# RUMBA_plus.net
KiCad netlist of a schematic drawn in Altium Designer
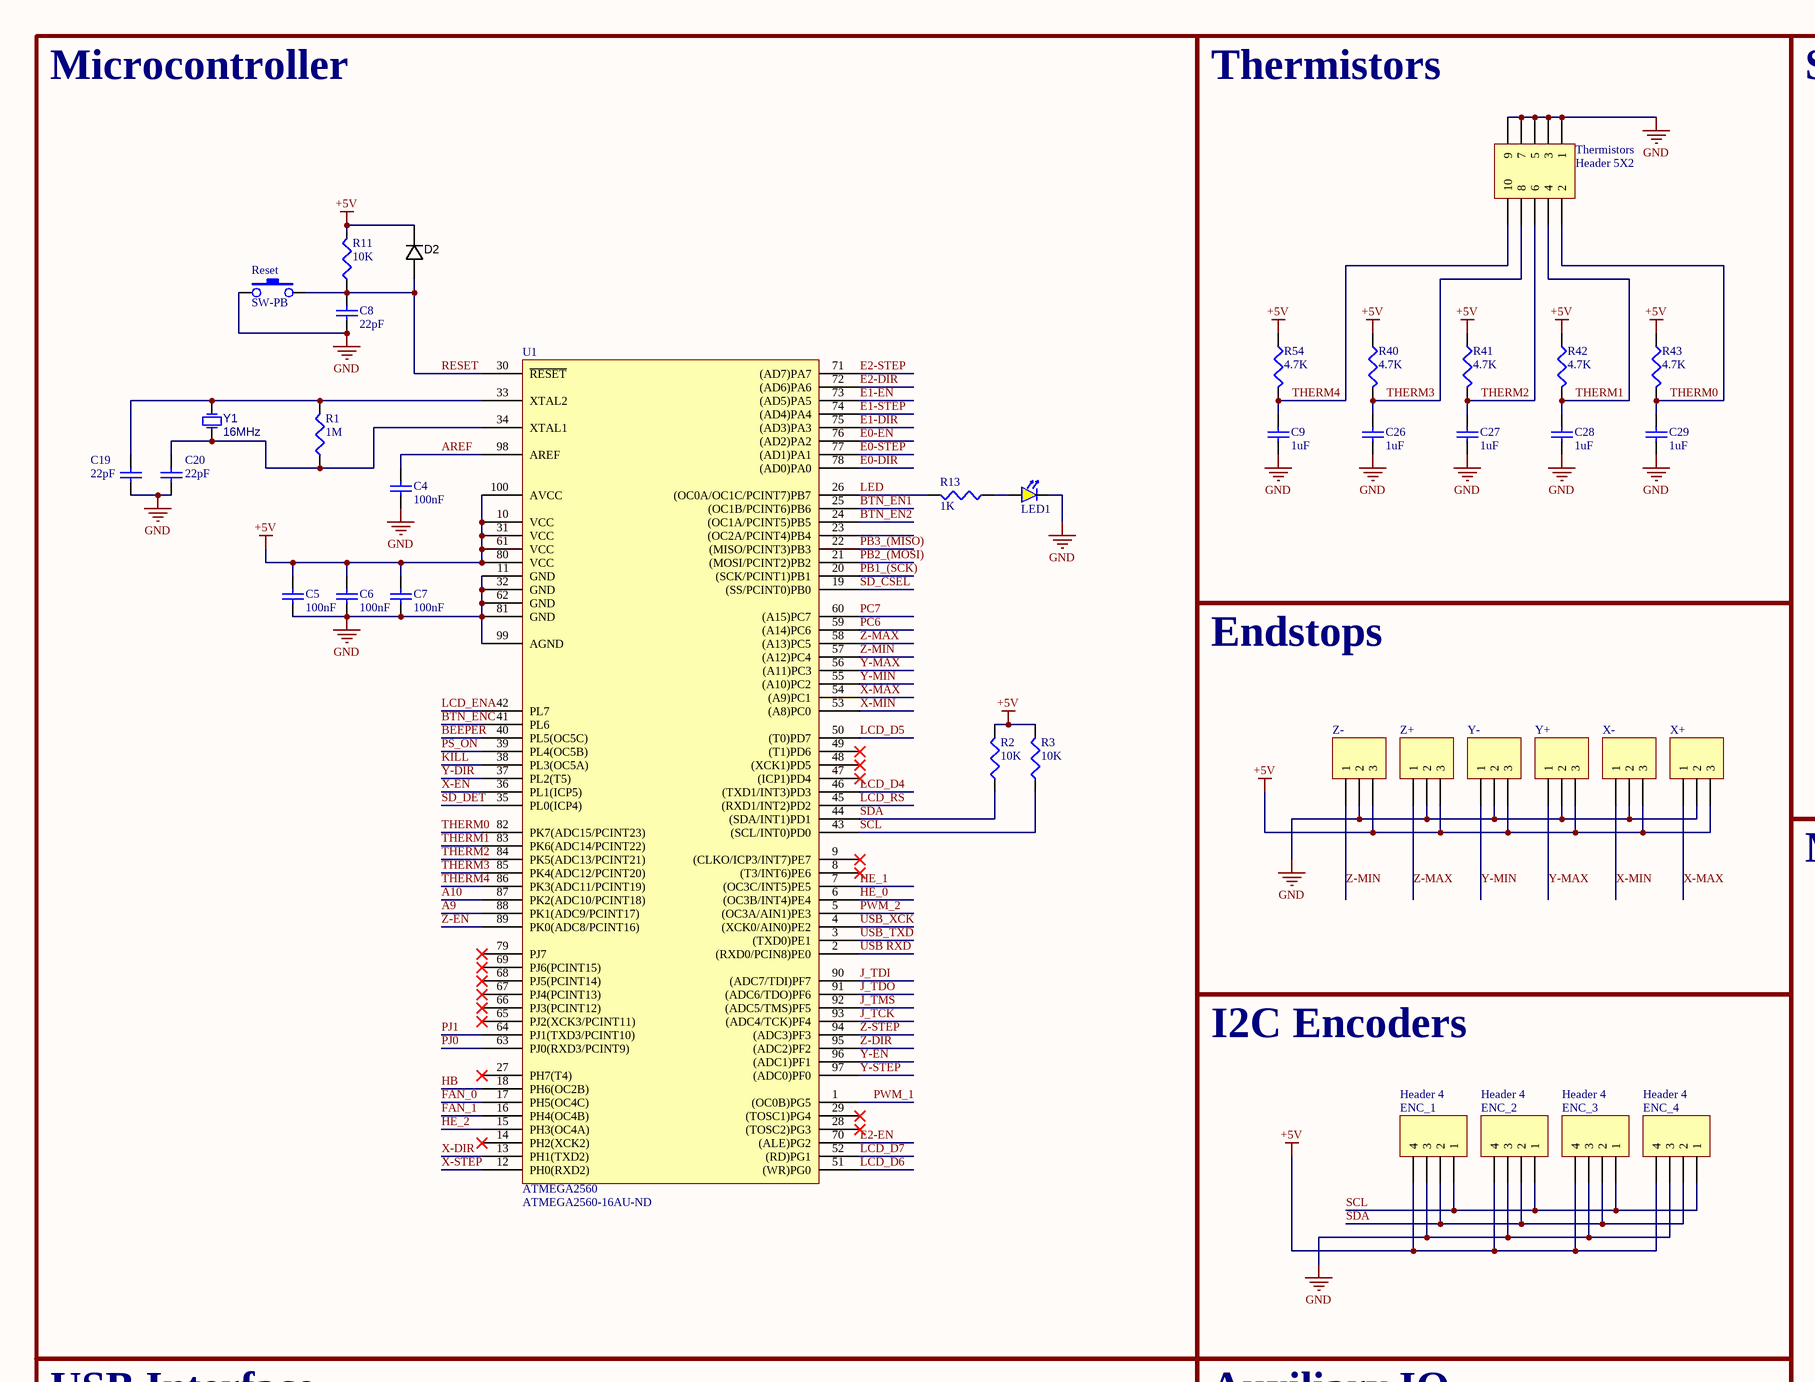
[diagram p0: RUMBA_plus.SchDoc, top left]
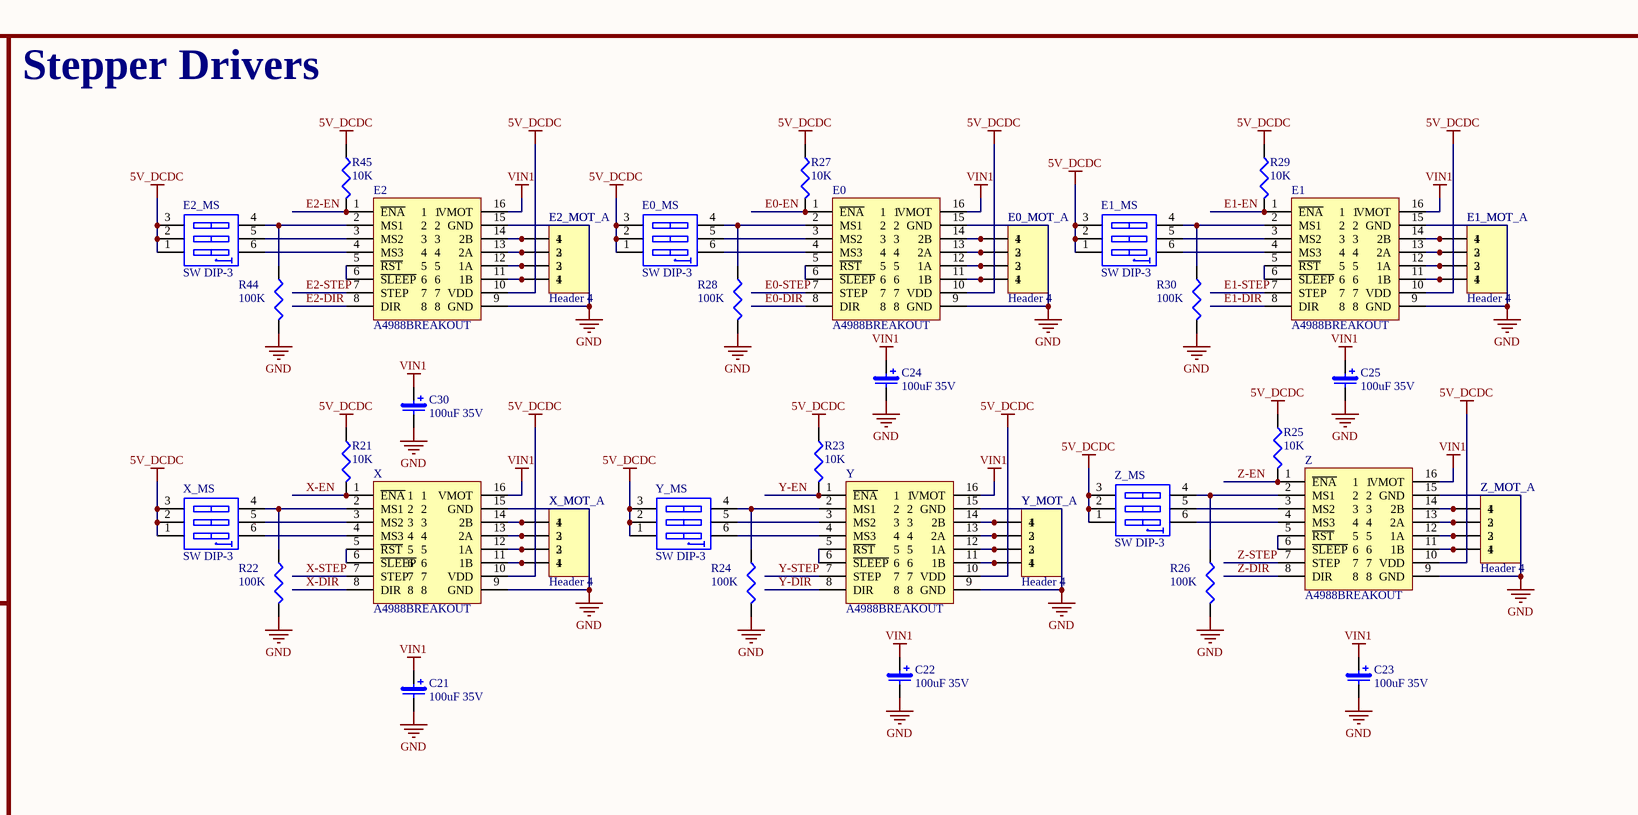
[diagram p1: RUMBA_plus.SchDoc, top right]
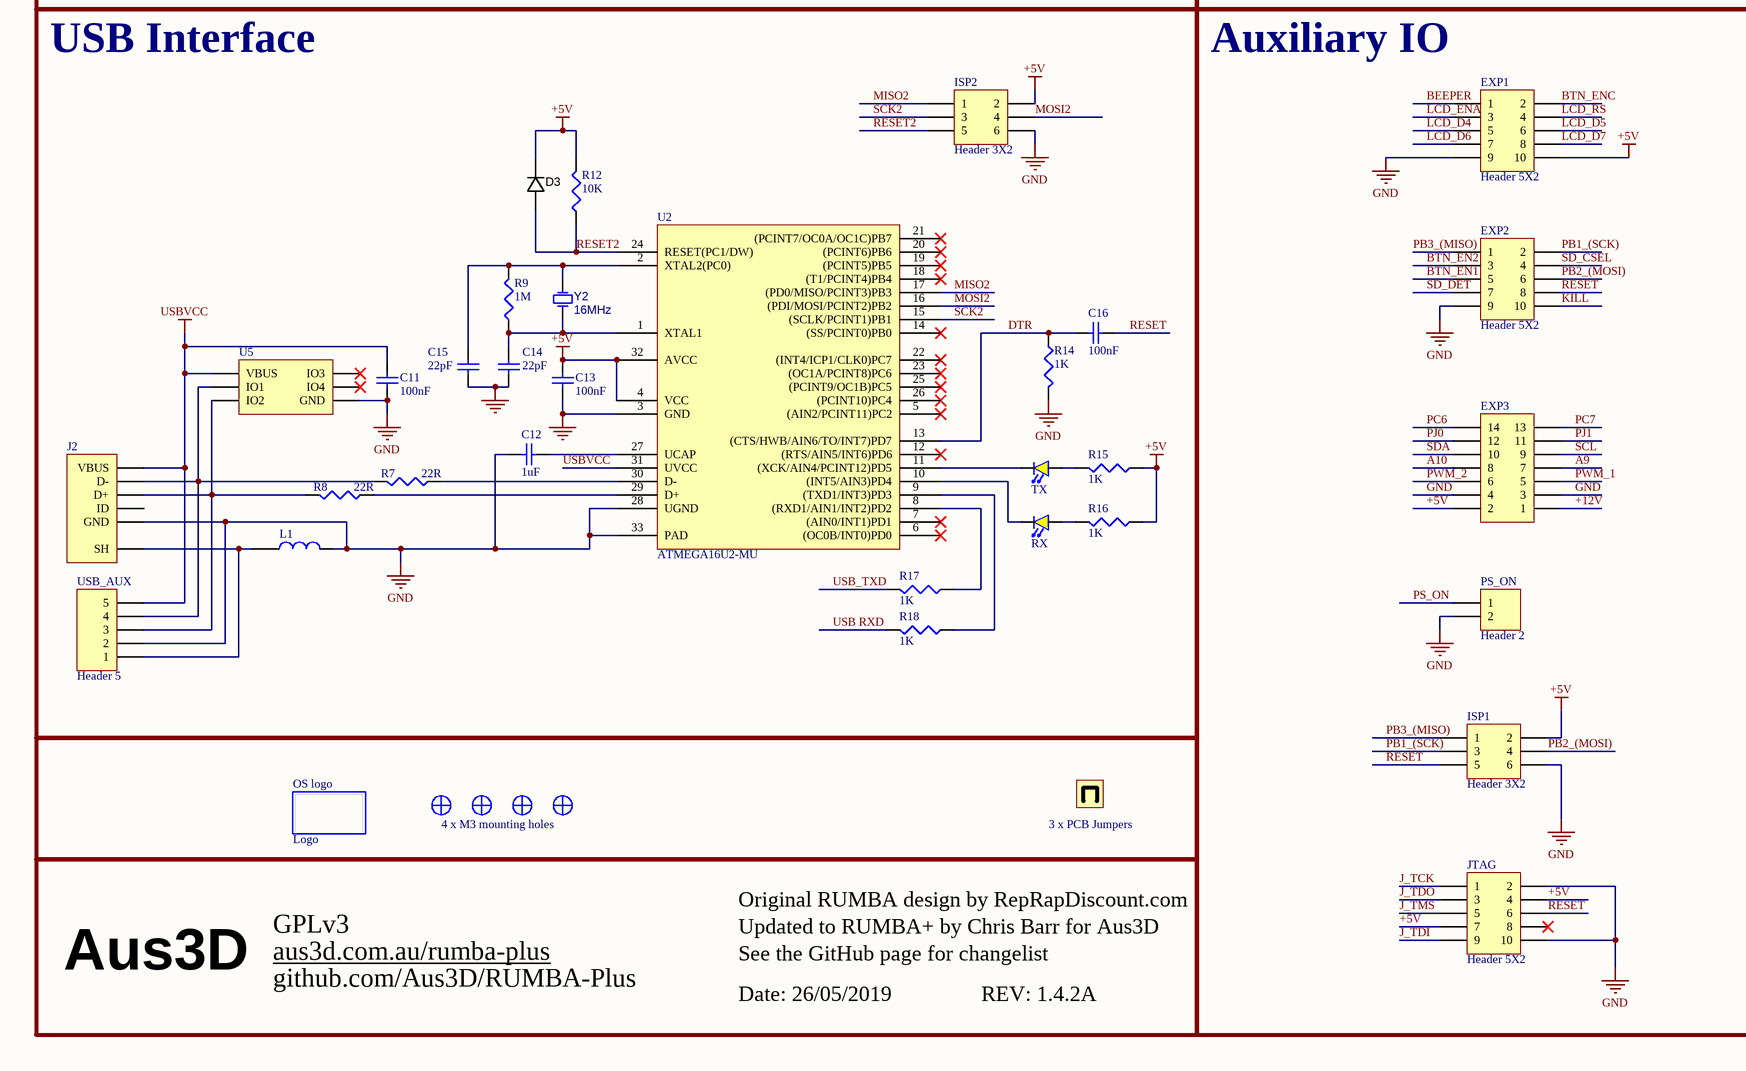
[diagram p2: RUMBA_plus.SchDoc, bottom left]
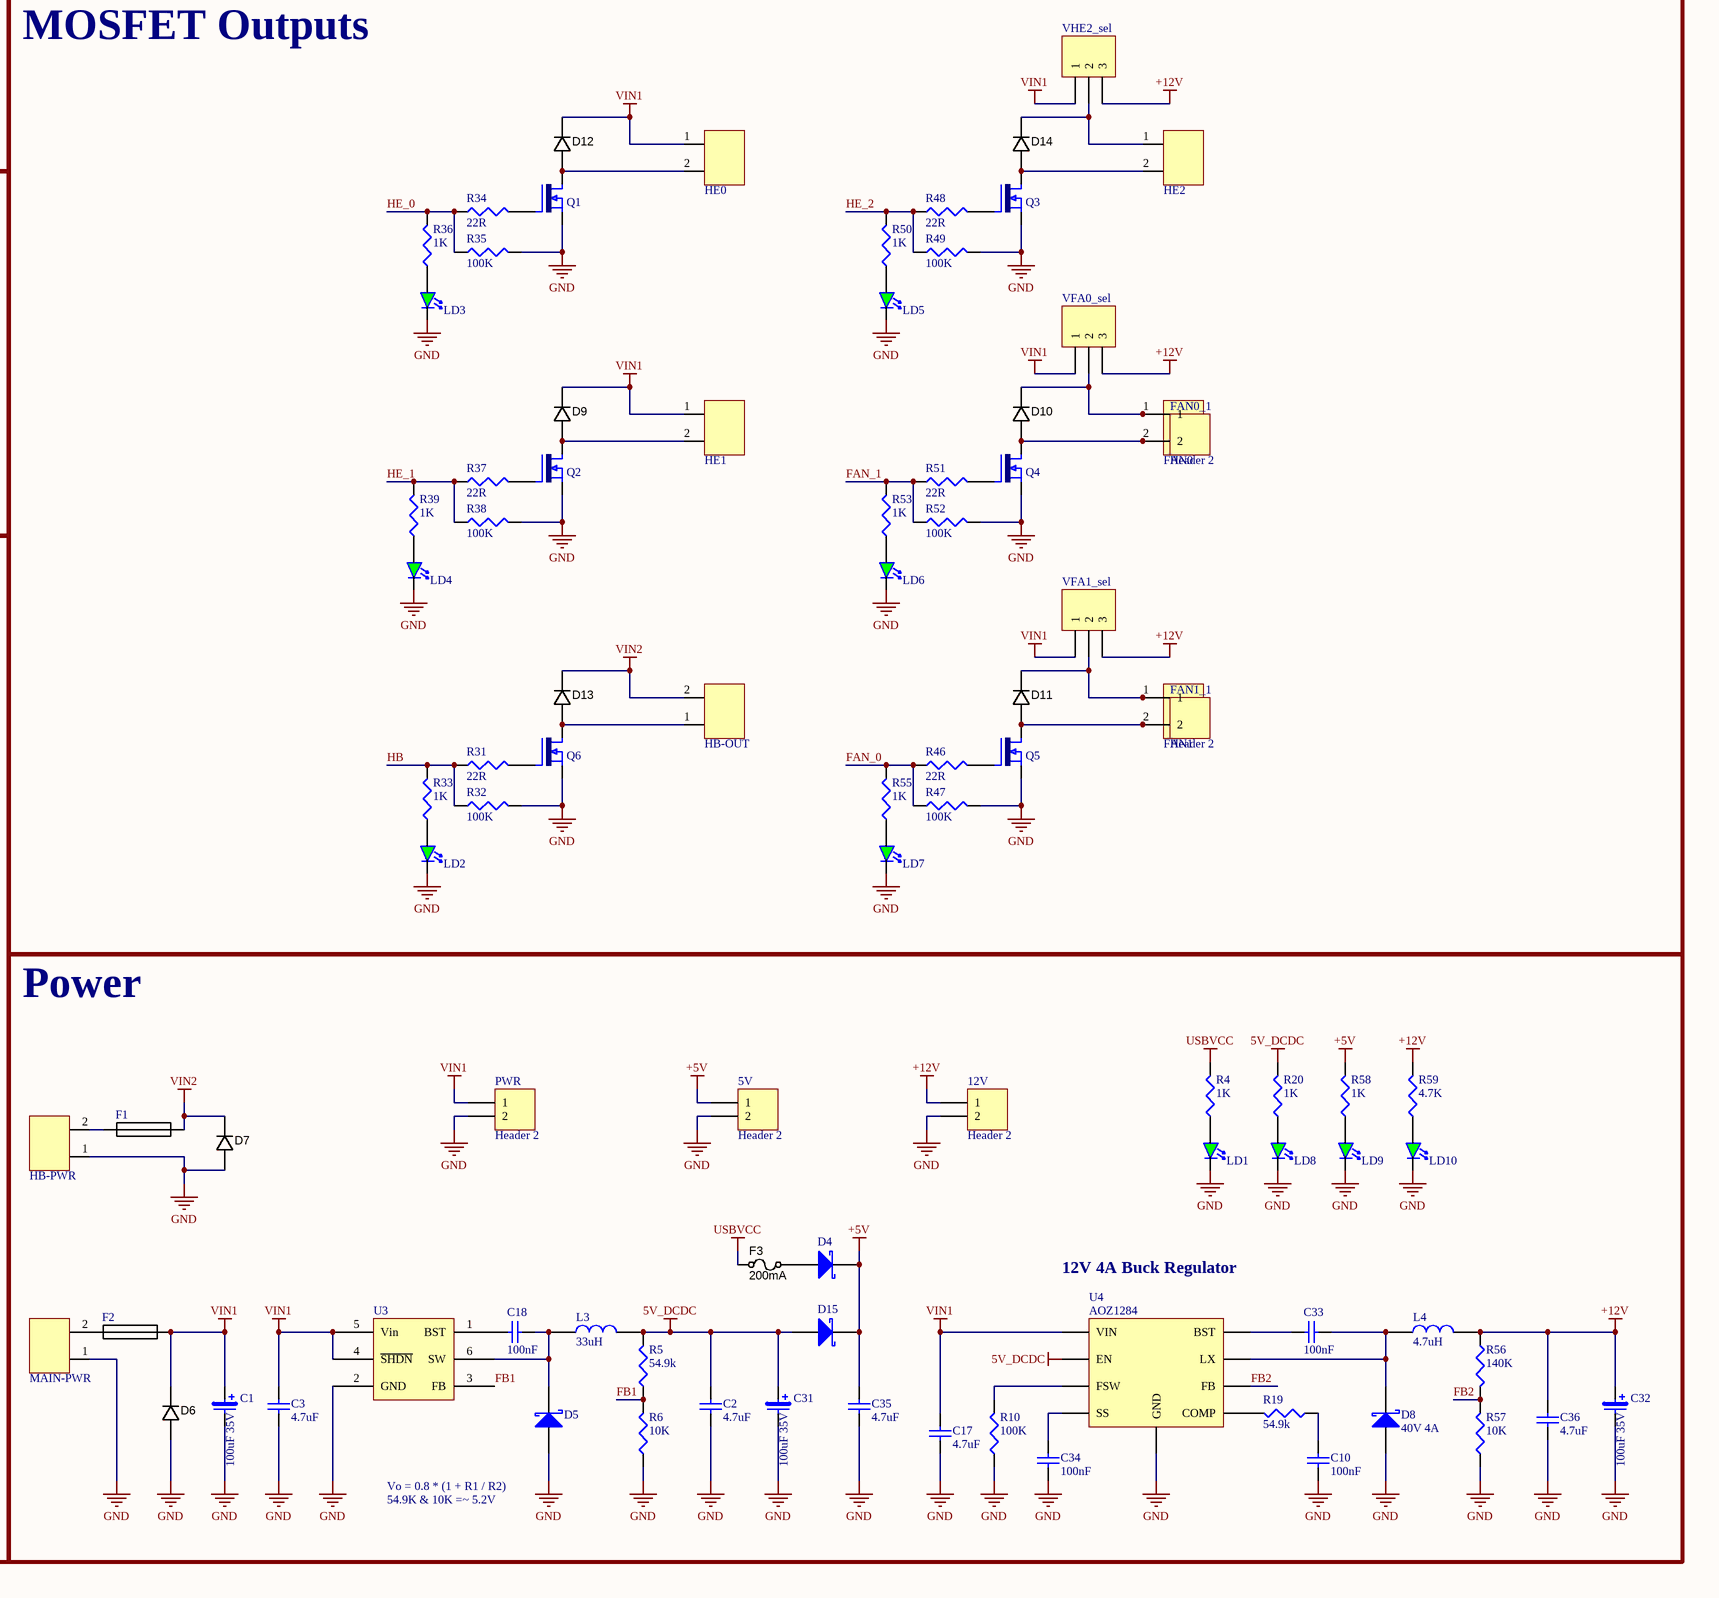
[diagram p3: RUMBA_plus.SchDoc, bottom right]

(export (version "E")
  (design (tool "Eeschema 10.0.6"))
  (components
    (comp (ref "5V")
      (value "Header 2")
      (footprint "HDR1X2")
      (description "Header, 2-Pin")
      (libsource (lib "RUMBA_v2") (part "Header 2"))
    )
    (comp (ref "12V")
      (value "Header 2")
      (footprint "HDR1X2")
      (description "Header, 2-Pin")
      (libsource (lib "RUMBA_v2") (part "Header 2"))
    )
    (comp (ref "C1")
      (value "100uF 35V")
      (footprint "CAP EL PANASONIC")
      (description "CAP ALUM 100UF 20% 35V SMD")
      (fields (field (name "PUBLISHER") "Altium Limited"))
      (libsource (lib "RUMBA_v2") (part "CapE-6.3-100uF-35V"))
    )
    (comp (ref "C2")
      (value "4.7uF")
      (footprint "CAPC2012X135N")
      (description "CAP CER 4.7UF 10V X7R 0805")
      (fields (field (name "TOLERANCE") "10%") (field (name "VOLTAGE") "10V"))
      (libsource (lib "main_library") (part "CapC-0805-4.7uF 10V"))
    )
    (comp (ref "C3")
      (value "4.7uF")
      (footprint "CAP 3225-1210")
      (description "CAP CER 4.7UF 50V X7R 1210")
      (fields (field (name "PUBLISHER") "Altium Limited"))
      (libsource (lib "picoprint_library") (part "CapC-1210-4.7uF-50V"))
    )
    (comp (ref "C4")
      (value "100nF")
      (footprint "Cap 1608-0603")
      (description "CAP CER 0.1UF 50V X7R 0603")
      (fields (field (name "PUBLISHER") "Altium Limited"))
      (libsource (lib "RUMBA_v2") (part "CapC-0603-100nF"))
    )
    (comp (ref "C5")
      (value "100nF")
      (footprint "Cap 1608-0603")
      (description "CAP CER 0.1UF 50V X7R 0603")
      (fields (field (name "PUBLISHER") "Altium Limited"))
      (libsource (lib "RUMBA_v2") (part "CapC-0603-100nF"))
    )
    (comp (ref "C6")
      (value "100nF")
      (footprint "Cap 1608-0603")
      (description "CAP CER 0.1UF 50V X7R 0603")
      (fields (field (name "PUBLISHER") "Altium Limited"))
      (libsource (lib "RUMBA_v2") (part "CapC-0603-100nF"))
    )
    (comp (ref "C7")
      (value "100nF")
      (footprint "Cap 1608-0603")
      (description "CAP CER 0.1UF 50V X7R 0603")
      (fields (field (name "PUBLISHER") "Altium Limited"))
      (libsource (lib "RUMBA_v2") (part "CapC-0603-100nF"))
    )
    (comp (ref "C8")
      (value "22pF")
      (footprint "Cap 1608-0603")
      (description "CAP CER 22PF 50V X7R 0603")
      (fields (field (name "PUBLISHER") "Altium Limited"))
      (libsource (lib "RUMBA_v2") (part "CapC-0603-22pF"))
    )
    (comp (ref "C9")
      (value "1uF")
      (footprint "Cap 1608-0603")
      (description "CAP CER 1UF 16V X7R 0603")
      (fields (field (name "VOLTAGE") "16V") (field (name "TOLERANCE") "10%"))
      (libsource (lib "main_library") (part "CapC-0603-1uF 50V"))
    )
    (comp (ref "C10")
      (value "100nF")
      (footprint "Cap 1608-0603")
      (description "CAP CER 0.1UF 50V X7R 0603")
      (fields (field (name "PUBLISHER") "Altium Limited"))
      (libsource (lib "RUMBA_v2") (part "CapC-0603-100nF"))
    )
    (comp (ref "C11")
      (value "100nF")
      (footprint "Cap 1608-0603")
      (description "CAP CER 0.1UF 50V X7R 0603")
      (fields (field (name "PUBLISHER") "Altium Limited"))
      (libsource (lib "RUMBA_v2") (part "CapC-0603-100nF"))
    )
    (comp (ref "C12")
      (value "1uF")
      (footprint "Cap 1608-0603")
      (description "CAP CER 1UF 16V X7R 0603")
      (fields (field (name "VOLTAGE") "16V") (field (name "TOLERANCE") "10%"))
      (libsource (lib "main_library") (part "CapC-0603-1uF 50V"))
    )
    (comp (ref "C13")
      (value "100nF")
      (footprint "Cap 1608-0603")
      (description "CAP CER 0.1UF 50V X7R 0603")
      (fields (field (name "PUBLISHER") "Altium Limited"))
      (libsource (lib "RUMBA_v2") (part "CapC-0603-100nF"))
    )
    (comp (ref "C14")
      (value "22pF")
      (footprint "Cap 1608-0603")
      (description "CAP CER 22PF 50V X7R 0603")
      (fields (field (name "PUBLISHER") "Altium Limited"))
      (libsource (lib "RUMBA_v2") (part "CapC-0603-22pF"))
    )
    (comp (ref "C15")
      (value "22pF")
      (footprint "Cap 1608-0603")
      (description "CAP CER 22PF 50V X7R 0603")
      (fields (field (name "PUBLISHER") "Altium Limited"))
      (libsource (lib "RUMBA_v2") (part "CapC-0603-22pF"))
    )
    (comp (ref "C16")
      (value "100nF")
      (footprint "Cap 1608-0603")
      (description "CAP CER 0.1UF 50V X7R 0603")
      (fields (field (name "PUBLISHER") "Altium Limited"))
      (libsource (lib "RUMBA_v2") (part "CapC-0603-100nF"))
    )
    (comp (ref "C17")
      (value "4.7uF")
      (footprint "CAP 3225-1210")
      (description "CAP CER 4.7UF 50V X7R 1210")
      (fields (field (name "PUBLISHER") "Altium Limited"))
      (libsource (lib "picoprint_library") (part "CapC-1210-4.7uF-50V"))
    )
    (comp (ref "C18")
      (value "100nF")
      (footprint "Cap 1608-0603")
      (description "CAP CER 0.1UF 50V X7R 0603")
      (fields (field (name "PUBLISHER") "Altium Limited"))
      (libsource (lib "RUMBA_v2") (part "CapC-0603-100nF"))
    )
    (comp (ref "C19")
      (value "22pF")
      (footprint "Cap 1608-0603")
      (description "CAP CER 22PF 50V X7R 0603")
      (fields (field (name "PUBLISHER") "Altium Limited"))
      (libsource (lib "RUMBA_v2") (part "CapC-0603-22pF"))
    )
    (comp (ref "C20")
      (value "22pF")
      (footprint "Cap 1608-0603")
      (description "CAP CER 22PF 50V X7R 0603")
      (fields (field (name "PUBLISHER") "Altium Limited"))
      (libsource (lib "RUMBA_v2") (part "CapC-0603-22pF"))
    )
    (comp (ref "C21")
      (value "100uF 35V")
      (footprint "CAP EL PANASONIC")
      (description "CAP ALUM 100UF 20% 35V SMD")
      (fields (field (name "PUBLISHER") "Altium Limited"))
      (libsource (lib "RUMBA_v2") (part "CapE-6.3-100uF-35V"))
    )
    (comp (ref "C22")
      (value "100uF 35V")
      (footprint "CAP EL PANASONIC")
      (description "CAP ALUM 100UF 20% 35V SMD")
      (fields (field (name "PUBLISHER") "Altium Limited"))
      (libsource (lib "RUMBA_v2") (part "CapE-6.3-100uF-35V"))
    )
    (comp (ref "C23")
      (value "100uF 35V")
      (footprint "CAP EL PANASONIC")
      (description "CAP ALUM 100UF 20% 35V SMD")
      (fields (field (name "PUBLISHER") "Altium Limited"))
      (libsource (lib "RUMBA_v2") (part "CapE-6.3-100uF-35V"))
    )
    (comp (ref "C24")
      (value "100uF 35V")
      (footprint "CAP EL PANASONIC")
      (description "CAP ALUM 100UF 20% 35V SMD")
      (fields (field (name "PUBLISHER") "Altium Limited"))
      (libsource (lib "RUMBA_v2") (part "CapE-6.3-100uF-35V"))
    )
    (comp (ref "C25")
      (value "100uF 35V")
      (footprint "CAP EL PANASONIC")
      (description "CAP ALUM 100UF 20% 35V SMD")
      (fields (field (name "PUBLISHER") "Altium Limited"))
      (libsource (lib "RUMBA_v2") (part "CapE-6.3-100uF-35V"))
    )
    (comp (ref "C26")
      (value "1uF")
      (footprint "Cap 1608-0603")
      (description "CAP CER 1UF 16V X7R 0603")
      (fields (field (name "VOLTAGE") "16V") (field (name "TOLERANCE") "10%"))
      (libsource (lib "main_library") (part "CapC-0603-1uF 50V"))
    )
    (comp (ref "C27")
      (value "1uF")
      (footprint "Cap 1608-0603")
      (description "CAP CER 1UF 16V X7R 0603")
      (fields (field (name "VOLTAGE") "16V") (field (name "TOLERANCE") "10%"))
      (libsource (lib "main_library") (part "CapC-0603-1uF 50V"))
    )
    (comp (ref "C28")
      (value "1uF")
      (footprint "Cap 1608-0603")
      (description "CAP CER 1UF 16V X7R 0603")
      (fields (field (name "VOLTAGE") "16V") (field (name "TOLERANCE") "10%"))
      (libsource (lib "main_library") (part "CapC-0603-1uF 50V"))
    )
    (comp (ref "C29")
      (value "1uF")
      (footprint "Cap 1608-0603")
      (description "CAP CER 1UF 16V X7R 0603")
      (fields (field (name "VOLTAGE") "16V") (field (name "TOLERANCE") "10%"))
      (libsource (lib "main_library") (part "CapC-0603-1uF 50V"))
    )
    (comp (ref "C30")
      (value "100uF 35V")
      (footprint "CAP EL PANASONIC")
      (description "CAP ALUM 100UF 20% 35V SMD")
      (fields (field (name "PUBLISHER") "Altium Limited"))
      (libsource (lib "RUMBA_v2") (part "CapE-6.3-100uF-35V"))
    )
    (comp (ref "C31")
      (value "100uF 35V")
      (footprint "CAP EL PANASONIC")
      (description "CAP ALUM 100UF 20% 35V SMD")
      (fields (field (name "PUBLISHER") "Altium Limited"))
      (libsource (lib "RUMBA_v2") (part "CapE-6.3-100uF-35V"))
    )
    (comp (ref "C32")
      (value "100uF 35V")
      (footprint "CAP EL PANASONIC")
      (description "CAP ALUM 100UF 20% 35V SMD")
      (fields (field (name "PUBLISHER") "Altium Limited"))
      (libsource (lib "RUMBA_v2") (part "CapE-6.3-100uF-35V"))
    )
    (comp (ref "C33")
      (value "100nF")
      (footprint "Cap 1608-0603")
      (description "CAP CER 0.1UF 50V X7R 0603")
      (fields (field (name "PUBLISHER") "Altium Limited"))
      (libsource (lib "RUMBA_v2") (part "CapC-0603-100nF"))
    )
    (comp (ref "C34")
      (value "100nF")
      (footprint "Cap 1608-0603")
      (description "CAP CER 0.1UF 50V X7R 0603")
      (fields (field (name "PUBLISHER") "Altium Limited"))
      (libsource (lib "RUMBA_v2") (part "CapC-0603-100nF"))
    )
    (comp (ref "C35")
      (value "4.7uF")
      (footprint "CAPC2012X135N")
      (description "CAP CER 4.7UF 10V X7R 0805")
      (fields (field (name "TOLERANCE") "10%") (field (name "VOLTAGE") "10V"))
      (libsource (lib "main_library") (part "CapC-0805-4.7uF 10V"))
    )
    (comp (ref "C36")
      (value "4.7uF")
      (footprint "CAP 3225-1210")
      (description "CAP CER 4.7UF 50V X7R 1210")
      (fields (field (name "PUBLISHER") "Altium Limited"))
      (libsource (lib "picoprint_library") (part "CapC-1210-4.7uF-50V"))
    )
    (comp (ref "D2")
      (value "~")
      (footprint "SOD323")
      (description "DIODE GEN PURP 75V 150MA SOD323")
      (libsource (lib "PBL - Diodes") (part "DIODE_75V_500mW"))
    )
    (comp (ref "D3")
      (value "~")
      (footprint "SOD323")
      (description "DIODE GEN PURP 75V 150MA SOD323")
      (libsource (lib "PBL - Diodes") (part "DIODE_75V_500mW"))
    )
    (comp (ref "D4")
      (value "~")
      (footprint "DIOM2616X08N")
      (description "DIODE SCHOTTKY 40V 2A SOD123F")
      (libsource (lib "picoprint_library") (part "Diode Schottky 2A 40V"))
    )
    (comp (ref "D5")
      (value "~")
      (footprint "DIOM2616X08N")
      (description "DIODE SCHOTTKY 40V 2A SOD123F")
      (libsource (lib "picoprint_library") (part "Diode Schottky 2A 40V"))
    )
    (comp (ref "D6")
      (value "~")
      (footprint "DO-214AC")
      (description "DIODE GEN PURP 100V 1.5A SMA")
      (libsource (lib "PBL - Diodes") (part "DIODE_100V_1.5A_SMA"))
    )
    (comp (ref "D7")
      (value "~")
      (footprint "DO-214AC")
      (description "DIODE GEN PURP 100V 1.5A SMA")
      (libsource (lib "PBL - Diodes") (part "DIODE_100V_1.5A_SMA"))
    )
    (comp (ref "D8")
      (value "40V 4A")
      (footprint "DO-214AA")
      (description "DIODE SCHOTTKY 40V 4A DO214AA")
      (libsource (lib "RUMBA_library") (part "Diode Schottky - 40V 4A - SSB44-E3"))
    )
    (comp (ref "D9")
      (value "~")
      (footprint "DO-214AC")
      (description "DIODE GEN PURP 100V 1.5A SMA")
      (libsource (lib "PBL - Diodes") (part "DIODE_100V_1.5A_SMA"))
    )
    (comp (ref "D10")
      (value "~")
      (footprint "DO-214AC")
      (description "DIODE GEN PURP 100V 1.5A SMA")
      (libsource (lib "PBL - Diodes") (part "DIODE_100V_1.5A_SMA"))
    )
    (comp (ref "D11")
      (value "~")
      (footprint "DO-214AC")
      (description "DIODE GEN PURP 100V 1.5A SMA")
      (libsource (lib "PBL - Diodes") (part "DIODE_100V_1.5A_SMA"))
    )
    (comp (ref "D12")
      (value "~")
      (footprint "DO-214AC")
      (description "DIODE GEN PURP 100V 1.5A SMA")
      (libsource (lib "PBL - Diodes") (part "DIODE_100V_1.5A_SMA"))
    )
    (comp (ref "D13")
      (value "~")
      (footprint "DO-214AC")
      (description "DIODE GEN PURP 100V 1.5A SMA")
      (libsource (lib "PBL - Diodes") (part "DIODE_100V_1.5A_SMA"))
    )
    (comp (ref "D14")
      (value "~")
      (footprint "DO-214AC")
      (description "DIODE GEN PURP 100V 1.5A SMA")
      (libsource (lib "PBL - Diodes") (part "DIODE_100V_1.5A_SMA"))
    )
    (comp (ref "D15")
      (value "~")
      (footprint "DIOM2616X08N")
      (description "DIODE SCHOTTKY 40V 2A SOD123F")
      (libsource (lib "picoprint_library") (part "Diode Schottky 2A 40V"))
    )
    (comp (ref "E0")
      (value "A4988BREAKOUT")
      (footprint "A4988BREAKOUT")
      (libsource (lib "RUMBA_v2") (part "A4988BREAKOUT"))
    )
    (comp (ref "E0_0")
      (value "~")
      (footprint "HDR1X8-HEADER")
      (description "Header, 8-Pin, Female")
      (libsource (lib "picoprint_library") (part "Header 8x1"))
    )
    (comp (ref "E0_1")
      (value "~")
      (footprint "HDR1X8-HEADER")
      (description "Header, 8-Pin, Female")
      (libsource (lib "picoprint_library") (part "Header 8x1"))
    )
    (comp (ref "E0_MOT")
      (value "~")
      (footprint "TERM4 3.5mm")
      (description "TERM BLK 4POS SIDE ENT 3.5MM PCB")
      (fields (field (name "PUBLISHER") "Altium Limited"))
      (libsource (lib "RUMBA_v2") (part "ScrewTerminal-3.5mm-4Way"))
    )
    (comp (ref "E0_MOT_A")
      (value "Header 4")
      (footprint "HDR1X4")
      (description "Header, 4-Pin")
      (libsource (lib "RUMBA_v2") (part "Header 4_1"))
    )
    (comp (ref "E0_MS")
      (value "SW DIP-3")
      (footprint "dipsw SO6")
      (description "SWITCH SLIDE DIP SPST 25MA 24V")
      (fields (field (name "PUBLISHER") "Altium Limited"))
      (libsource (lib "RUMBA_v2") (part "SW DIP-3"))
    )
    (comp (ref "E1")
      (value "A4988BREAKOUT")
      (footprint "A4988BREAKOUT")
      (libsource (lib "RUMBA_v2") (part "A4988BREAKOUT"))
    )
    (comp (ref "E1_0")
      (value "~")
      (footprint "HDR1X8-HEADER")
      (description "Header, 8-Pin, Female")
      (libsource (lib "picoprint_library") (part "Header 8x1"))
    )
    (comp (ref "E1_1")
      (value "~")
      (footprint "HDR1X8-HEADER")
      (description "Header, 8-Pin, Female")
      (libsource (lib "picoprint_library") (part "Header 8x1"))
    )
    (comp (ref "E1_MOT")
      (value "~")
      (footprint "TERM4 3.5mm")
      (description "TERM BLK 4POS SIDE ENT 3.5MM PCB")
      (fields (field (name "PUBLISHER") "Altium Limited"))
      (libsource (lib "RUMBA_v2") (part "ScrewTerminal-3.5mm-4Way"))
    )
    (comp (ref "E1_MOT_A")
      (value "Header 4")
      (footprint "HDR1X4")
      (description "Header, 4-Pin")
      (libsource (lib "RUMBA_v2") (part "Header 4_1"))
    )
    (comp (ref "E1_MS")
      (value "SW DIP-3")
      (footprint "dipsw SO6")
      (description "SWITCH SLIDE DIP SPST 25MA 24V")
      (fields (field (name "PUBLISHER") "Altium Limited"))
      (libsource (lib "RUMBA_v2") (part "SW DIP-3"))
    )
    (comp (ref "E2")
      (value "A4988BREAKOUT")
      (footprint "A4988BREAKOUT")
      (libsource (lib "RUMBA_v2") (part "A4988BREAKOUT"))
    )
    (comp (ref "E2_0")
      (value "~")
      (footprint "HDR1X8-HEADER")
      (description "Header, 8-Pin, Female")
      (libsource (lib "picoprint_library") (part "Header 8x1"))
    )
    (comp (ref "E2_1")
      (value "~")
      (footprint "HDR1X8-HEADER")
      (description "Header, 8-Pin, Female")
      (libsource (lib "picoprint_library") (part "Header 8x1"))
    )
    (comp (ref "E2_MOT")
      (value "~")
      (footprint "TERM4 3.5mm")
      (description "TERM BLK 4POS SIDE ENT 3.5MM PCB")
      (fields (field (name "PUBLISHER") "Altium Limited"))
      (libsource (lib "RUMBA_v2") (part "ScrewTerminal-3.5mm-4Way"))
    )
    (comp (ref "E2_MOT_A")
      (value "Header 4")
      (footprint "HDR1X4")
      (description "Header, 4-Pin")
      (libsource (lib "RUMBA_v2") (part "Header 4_1"))
    )
    (comp (ref "E2_MS")
      (value "SW DIP-3")
      (footprint "dipsw SO6")
      (description "SWITCH SLIDE DIP SPST 25MA 24V")
      (libsource (lib "RUMBA_v2") (part "SW DIP-3"))
    )
    (comp (ref "ENC_1")
      (value "Header 4")
      (footprint "HDR1X4")
      (description "Header, 4-Pin")
      (libsource (lib "Miscellaneous Connectors") (part "Header 4"))
    )
    (comp (ref "ENC_2")
      (value "Header 4")
      (footprint "HDR1X4")
      (description "Header, 4-Pin")
      (libsource (lib "Miscellaneous Connectors") (part "Header 4"))
    )
    (comp (ref "ENC_3")
      (value "Header 4")
      (footprint "HDR1X4")
      (description "Header, 4-Pin")
      (libsource (lib "Miscellaneous Connectors") (part "Header 4"))
    )
    (comp (ref "ENC_4")
      (value "Header 4")
      (footprint "HDR1X4")
      (description "Header, 4-Pin")
      (libsource (lib "Miscellaneous Connectors") (part "Header 4"))
    )
    (comp (ref "EXP1")
      (value "Header 5X2")
      (footprint "HDR2X5_exp Iner only\\")
      (description "Header, 5-Pin, Dual row")
      (libsource (lib "RUMBA_v2") (part "Header 5X2"))
    )
    (comp (ref "EXP2")
      (value "Header 5X2")
      (footprint "HDR2X5_exp Iner only\\")
      (description "Header, 5-Pin, Dual row")
      (libsource (lib "RUMBA_v2") (part "Header 5X2"))
    )
    (comp (ref "EXP3")
      (value "Header 7X2")
      (footprint "HDR2X7")
      (description "Header, 7-Pin, Dual row")
      (libsource (lib "RUMBA_v2") (part "Header 7X2"))
    )
    (comp (ref "F1")
      (value "~")
      (footprint "Fuseholder - BK-6013 - Mini ATC ATO Blade 15A")
      (description "FUSE HOLDER BLADE PCB")
      (libsource (lib "Schlib1") (part "Fuseholder - Mini ATC ATO 15A"))
    )
    (comp (ref "F2")
      (value "~")
      (footprint "Fuseholder - BK-6013 - Mini ATC ATO Blade 15A")
      (description "FUSE HOLDER BLADE PCB")
      (libsource (lib "Schlib1") (part "Fuseholder - Mini ATC ATO 15A"))
    )
    (comp (ref "F3")
      (value "200mA")
      (footprint "PTC Fuse1608-0603")
      (description "PTC RESET FUSE 9V 200MA 0603")
      (libsource (lib "Schlib1") (part "Fuse - 15V 200mA Trip PTC SMD 0603"))
    )
    (comp (ref "FAN0")
      (value "~")
      (footprint "TERM2 3.5mm")
      (description "TERM BLK 2POS SIDE ENT 3.5MM PCB")
      (libsource (lib "RUMBA_v2") (part "ScrewTerminal-3.5mm-2Way"))
    )
    (comp (ref "FAN0_1")
      (value "Header 2")
      (footprint "HDR1X2")
      (description "Header, 2-Pin")
      (libsource (lib "") (part "Header 2_1"))
    )
    (comp (ref "FAN1")
      (value "~")
      (footprint "TERM2 3.5mm")
      (description "TERM BLK 2POS SIDE ENT 3.5MM PCB")
      (libsource (lib "RUMBA_v2") (part "ScrewTerminal-3.5mm-2Way"))
    )
    (comp (ref "FAN1_1")
      (value "Header 2")
      (footprint "HDR1X2")
      (description "Header, 2-Pin")
      (libsource (lib "") (part "Header 2_1"))
    )
    (comp (ref "HB-OUT")
      (value "~")
      (footprint "TERM2 5MM")
      (description "TERM BLK 2POS SIDE ENTRY 5MM PCB")
      (libsource (lib "") (part "ScrewTerminal-5mm-2Way_1"))
    )
    (comp (ref "HB-PWR")
      (value "~")
      (footprint "TERM2 5MM")
      (description "TERM BLK 2POS SIDE ENTRY 5MM PCB")
      (libsource (lib "RUMBA_v2") (part "ScrewTerminal-5mm-2Way"))
    )
    (comp (ref "HE0")
      (value "~")
      (footprint "TERM2 3.5mm")
      (description "TERM BLK 2POS SIDE ENT 3.5MM PCB")
      (libsource (lib "RUMBA_v2") (part "ScrewTerminal-3.5mm-2Way"))
    )
    (comp (ref "HE1")
      (value "~")
      (footprint "TERM2 3.5mm")
      (description "TERM BLK 2POS SIDE ENT 3.5MM PCB")
      (libsource (lib "RUMBA_v2") (part "ScrewTerminal-3.5mm-2Way"))
    )
    (comp (ref "HE2")
      (value "~")
      (footprint "TERM2 3.5mm")
      (description "TERM BLK 2POS SIDE ENT 3.5MM PCB")
      (libsource (lib "RUMBA_v2") (part "ScrewTerminal-3.5mm-2Way"))
    )
    (comp (ref "ISP1")
      (value "Header 3X2")
      (footprint "HDR2X3")
      (description "Header, 3-Pin, Dual row")
      (libsource (lib "RUMBA_v2") (part "Header 3X2"))
    )
    (comp (ref "ISP2")
      (value "Header 3X2")
      (footprint "HDR2X3")
      (description "Header, 3-Pin, Dual row")
      (libsource (lib "RUMBA_v2") (part "Header 3X2"))
    )
    (comp (ref "J2")
      (value "~")
      (footprint "Micro-USB B Molex 105017-0001")
      (description "CONN RCPT USB2.0 MICRO B SMD R/A")
      (libsource (lib "picoprint_library") (part "Micro-USB B Socket"))
    )
    (comp (ref "JTAG")
      (value "Header 5X2")
      (footprint "HDR2X5")
      (description "Header, 5-Pin, Dual row")
      (libsource (lib "RUMBA_v2") (part "Header 5X2"))
    )
    (comp (ref "L1")
      (value "~")
      (footprint "Res 2012-0805")
      (description "FERRITE BEAD 220 OHM 0805 1LN")
      (libsource (lib "RUMBA_v2") (part "Ferrite Bead SMD 0805"))
    )
    (comp (ref "L3")
      (value "33uH")
      (footprint "SRN6045TA SMD Inductor")
      (description "FIXED IND 33UH 1.8A 145 MOHM SMD")
      (libsource (lib "RUMBA_v2") (part "Inductor SMD 33uH 2.5A"))
    )
    (comp (ref "L4")
      (value "4.7uH")
      (footprint "SRN6045TA SMD Inductor")
      (description "FIXED IND 4.7UH 4.5A 26 MOHM SMD")
      (fields (field (name "PUBLISHER") "Altium Limited"))
      (libsource (lib "RUMBA_v2") (part "Inductor SMD 33uH 2.5A"))
    )
    (comp (ref "LD1")
      (value "~")
      (footprint "LED 1608-0603")
      (description "LED GREEN CLEAR CHIP SMD 0603")
      (libsource (lib "picoprint_library") (part "LEDG  0603"))
    )
    (comp (ref "LD2")
      (value "~")
      (footprint "LED 1608-0603")
      (description "LED GREEN CLEAR CHIP SMD 0603")
      (libsource (lib "picoprint_library") (part "LEDG  0603"))
    )
    (comp (ref "LD3")
      (value "~")
      (footprint "LED 1608-0603")
      (description "LED GREEN CLEAR CHIP SMD 0603")
      (libsource (lib "picoprint_library") (part "LEDG  0603"))
    )
    (comp (ref "LD4")
      (value "~")
      (footprint "LED 1608-0603")
      (description "LED GREEN CLEAR CHIP SMD 0603")
      (libsource (lib "picoprint_library") (part "LEDG  0603"))
    )
    (comp (ref "LD5")
      (value "~")
      (footprint "LED 1608-0603")
      (description "LED GREEN CLEAR CHIP SMD 0603")
      (libsource (lib "picoprint_library") (part "LEDG  0603"))
    )
    (comp (ref "LD6")
      (value "~")
      (footprint "LED 1608-0603")
      (description "LED GREEN CLEAR CHIP SMD 0603")
      (libsource (lib "picoprint_library") (part "LEDG  0603"))
    )
    (comp (ref "LD7")
      (value "~")
      (footprint "LED 1608-0603")
      (description "LED GREEN CLEAR CHIP SMD 0603")
      (libsource (lib "picoprint_library") (part "LEDG  0603"))
    )
    (comp (ref "LD8")
      (value "~")
      (footprint "LED 1608-0603")
      (description "LED GREEN CLEAR CHIP SMD 0603")
      (libsource (lib "picoprint_library") (part "LEDG  0603"))
    )
    (comp (ref "LD9")
      (value "~")
      (footprint "LED 1608-0603")
      (description "LED GREEN CLEAR CHIP SMD 0603")
      (libsource (lib "picoprint_library") (part "LEDG  0603"))
    )
    (comp (ref "LD10")
      (value "~")
      (footprint "LED 1608-0603")
      (description "LED GREEN CLEAR CHIP SMD 0603")
      (libsource (lib "picoprint_library") (part "LEDG  0603"))
    )
    (comp (ref "LED1")
      (value "~")
      (footprint "LED 1608-0603")
      (description "LED YELLOW CLEAR CHIP SMD 0603")
      (libsource (lib "picoprint_library") (part "LEDY  0603"))
    )
    (comp (ref "MAIN-PWR")
      (value "~")
      (footprint "TERM2 5MM")
      (description "TERM BLK 2POS SIDE ENTRY 5MM PCB")
      (libsource (lib "RUMBA_v2") (part "ScrewTerminal-5mm-2Way"))
    )
    (comp (ref "OS logo") (value "Logo") (footprint "OS LOGO TOP") (libsource (lib "gc") (part "Logo")))
    (comp (ref "PS_ON")
      (value "Header 2")
      (footprint "HDR1X2")
      (description "Header, 2-Pin")
      (libsource (lib "RUMBA_v2") (part "Header 2"))
    )
    (comp (ref "PWR")
      (value "Header 2")
      (footprint "HDR1X2")
      (description "Header, 2-Pin")
      (libsource (lib "RUMBA_v2") (part "Header 2"))
    )
    (comp (ref "Q1")
      (value "~")
      (footprint "LFPACK")
      (description "MOSFET N-CH 40V 33A LFPAK")
      (libsource (lib "RUMBA_library") (part "MOSFET - BUK9Y21-40E"))
    )
    (comp (ref "Q2")
      (value "~")
      (footprint "LFPACK")
      (description "MOSFET N-CH 40V 33A LFPAK")
      (libsource (lib "RUMBA_library") (part "MOSFET - BUK9Y21-40E"))
    )
    (comp (ref "Q3")
      (value "~")
      (footprint "LFPACK")
      (description "MOSFET N-CH 40V 33A LFPAK")
      (libsource (lib "RUMBA_library") (part "MOSFET - BUK9Y21-40E"))
    )
    (comp (ref "Q4")
      (value "~")
      (footprint "LFPACK")
      (description "MOSFET N-CH 40V 33A LFPAK")
      (libsource (lib "RUMBA_library") (part "MOSFET - BUK9Y21-40E"))
    )
    (comp (ref "Q5")
      (value "~")
      (footprint "LFPACK")
      (description "MOSFET N-CH 40V 33A LFPAK")
      (libsource (lib "RUMBA_library") (part "MOSFET - BUK9Y21-40E"))
    )
    (comp (ref "Q6")
      (value "~")
      (footprint "LFPACK")
      (description "MOSFET N-CH 40V 100A LFPAK")
      (libsource (lib "RUMBA_library") (part "MOSFET - PSMN1R8-40YLC"))
    )
    (comp (ref "R1")
      (value "1M")
      (footprint "RES 1608-0603")
      (description "RES SMD 1M OHM 1% 1/10W 0603")
      (fields (field (name "PUBLISHER") "Altium Limited"))
      (libsource (lib "RUMBA_v2") (part "Res-0603-1M"))
    )
    (comp (ref "R2")
      (value "10K")
      (footprint "RES 1608-0603")
      (description "RES SMD 10K OHM 1% 1/10W 0603")
      (fields (field (name "PUBLISHER") "Altium Limited"))
      (libsource (lib "RUMBA_v2") (part "Res-0603-10K"))
    )
    (comp (ref "R3")
      (value "10K")
      (footprint "RES 1608-0603")
      (description "RES SMD 10K OHM 1% 1/10W 0603")
      (fields (field (name "PUBLISHER") "Altium Limited"))
      (libsource (lib "RUMBA_v2") (part "Res-0603-10K"))
    )
    (comp (ref "R4")
      (value "1K")
      (footprint "RES 1608-0603")
      (description "RES SMD 1K OHM 1% 1/10W 0603")
      (fields (field (name "PUBLISHER") "Altium Limited"))
      (libsource (lib "RUMBA_v2") (part "Res-0603-1K"))
    )
    (comp (ref "R5")
      (value "54.9k")
      (footprint "RES 1608-0603")
      (description "RES SMD 54.9K OHM 1% 1/10W 0603")
      (fields (field (name "PUBLISHER") "Altium Limited"))
      (libsource (lib "RUMBA_v2") (part "Res-0603-10K"))
    )
    (comp (ref "R6")
      (value "10K")
      (footprint "RES 1608-0603")
      (description "RES SMD 10K OHM 1% 1/10W 0603")
      (fields (field (name "PUBLISHER") "Altium Limited"))
      (libsource (lib "RUMBA_v2") (part "Res-0603-10K"))
    )
    (comp (ref "R7")
      (value "22R")
      (footprint "RES 1608-0603")
      (description "RES SMD 22 OHM 1% 1/10W 0603")
      (fields (field (name "PUBLISHER") "Altium Limited"))
      (libsource (lib "RUMBA_v2") (part "Res-0603-22R"))
    )
    (comp (ref "R8")
      (value "22R")
      (footprint "RES 1608-0603")
      (description "RES SMD 22 OHM 1% 1/10W 0603")
      (fields (field (name "PUBLISHER") "Altium Limited"))
      (libsource (lib "RUMBA_v2") (part "Res-0603-22R"))
    )
    (comp (ref "R9")
      (value "1M")
      (footprint "RES 1608-0603")
      (description "RES SMD 1M OHM 1% 1/10W 0603")
      (fields (field (name "PUBLISHER") "Altium Limited"))
      (libsource (lib "RUMBA_v2") (part "Res-0603-1M"))
    )
    (comp (ref "R10")
      (value "100K")
      (footprint "RES 1608-0603")
      (description "RES SMD 100K OHM 1% 1/10W 0603")
      (fields (field (name "PUBLISHER") "Altium Limited"))
      (libsource (lib "RUMBA_v2") (part "Res-0603-100K"))
    )
    (comp (ref "R11")
      (value "10K")
      (footprint "RES 1608-0603")
      (description "RES SMD 10K OHM 1% 1/10W 0603")
      (fields (field (name "PUBLISHER") "Altium Limited"))
      (libsource (lib "RUMBA_v2") (part "Res-0603-10K"))
    )
    (comp (ref "R12")
      (value "10K")
      (footprint "RES 1608-0603")
      (description "RES SMD 10K OHM 1% 1/10W 0603")
      (fields (field (name "PUBLISHER") "Altium Limited"))
      (libsource (lib "RUMBA_v2") (part "Res-0603-10K"))
    )
    (comp (ref "R13")
      (value "1K")
      (footprint "RES 1608-0603")
      (description "RES SMD 1K OHM 1% 1/10W 0603")
      (fields (field (name "PUBLISHER") "Altium Limited"))
      (libsource (lib "RUMBA_v2") (part "Res-0603-1K"))
    )
    (comp (ref "R14")
      (value "1K")
      (footprint "RES 1608-0603")
      (description "RES SMD 1K OHM 1% 1/10W 0603")
      (fields (field (name "PUBLISHER") "Altium Limited"))
      (libsource (lib "RUMBA_v2") (part "Res-0603-1K"))
    )
    (comp (ref "R15")
      (value "1K")
      (footprint "RES 1608-0603")
      (description "RES SMD 1K OHM 1% 1/10W 0603")
      (fields (field (name "PUBLISHER") "Altium Limited"))
      (libsource (lib "RUMBA_v2") (part "Res-0603-1K"))
    )
    (comp (ref "R16")
      (value "1K")
      (footprint "RES 1608-0603")
      (description "RES SMD 1K OHM 1% 1/10W 0603")
      (fields (field (name "PUBLISHER") "Altium Limited"))
      (libsource (lib "RUMBA_v2") (part "Res-0603-1K"))
    )
    (comp (ref "R17")
      (value "1K")
      (footprint "RES 1608-0603")
      (description "RES SMD 1K OHM 1% 1/10W 0603")
      (fields (field (name "PUBLISHER") "Altium Limited"))
      (libsource (lib "RUMBA_v2") (part "Res-0603-1K"))
    )
    (comp (ref "R18")
      (value "1K")
      (footprint "RES 1608-0603")
      (description "RES SMD 1K OHM 1% 1/10W 0603")
      (fields (field (name "PUBLISHER") "Altium Limited"))
      (libsource (lib "RUMBA_v2") (part "Res-0603-1K"))
    )
    (comp (ref "R19")
      (value "54.9k")
      (footprint "RES 1608-0603")
      (description "RES SMD 54.9K OHM 1% 1/10W 0603")
      (fields (field (name "PUBLISHER") "Altium Limited"))
      (libsource (lib "RUMBA_v2") (part "Res-0603-10K"))
    )
    (comp (ref "R20")
      (value "1K")
      (footprint "RES 1608-0603")
      (description "RES SMD 1K OHM 1% 1/10W 0603")
      (fields (field (name "PUBLISHER") "Altium Limited"))
      (libsource (lib "RUMBA_v2") (part "Res-0603-1K"))
    )
    (comp (ref "R21")
      (value "10K")
      (footprint "RES 1608-0603")
      (description "RES SMD 10K OHM 1% 1/10W 0603")
      (fields (field (name "PUBLISHER") "Altium Limited"))
      (libsource (lib "RUMBA_v2") (part "Res-0603-10K"))
    )
    (comp (ref "R22")
      (value "100K")
      (footprint "RES 1608-0603")
      (description "RES SMD 100K OHM 1% 1/10W 0603")
      (fields (field (name "PUBLISHER") "Altium Limited"))
      (libsource (lib "RUMBA_v2") (part "Res-0603-100K"))
    )
    (comp (ref "R23")
      (value "10K")
      (footprint "RES 1608-0603")
      (description "RES SMD 10K OHM 1% 1/10W 0603")
      (fields (field (name "PUBLISHER") "Altium Limited"))
      (libsource (lib "RUMBA_v2") (part "Res-0603-10K"))
    )
    (comp (ref "R24")
      (value "100K")
      (footprint "RES 1608-0603")
      (description "RES SMD 100K OHM 1% 1/10W 0603")
      (fields (field (name "PUBLISHER") "Altium Limited"))
      (libsource (lib "RUMBA_v2") (part "Res-0603-100K"))
    )
    (comp (ref "R25")
      (value "10K")
      (footprint "RES 1608-0603")
      (description "RES SMD 10K OHM 1% 1/10W 0603")
      (fields (field (name "PUBLISHER") "Altium Limited"))
      (libsource (lib "RUMBA_v2") (part "Res-0603-10K"))
    )
    (comp (ref "R26")
      (value "100K")
      (footprint "RES 1608-0603")
      (description "RES SMD 100K OHM 1% 1/10W 0603")
      (fields (field (name "PUBLISHER") "Altium Limited"))
      (libsource (lib "RUMBA_v2") (part "Res-0603-100K"))
    )
    (comp (ref "R27")
      (value "10K")
      (footprint "RES 1608-0603")
      (description "RES SMD 10K OHM 1% 1/10W 0603")
      (fields (field (name "PUBLISHER") "Altium Limited"))
      (libsource (lib "RUMBA_v2") (part "Res-0603-10K"))
    )
    (comp (ref "R28")
      (value "100K")
      (footprint "RES 1608-0603")
      (description "RES SMD 100K OHM 1% 1/10W 0603")
      (fields (field (name "PUBLISHER") "Altium Limited"))
      (libsource (lib "RUMBA_v2") (part "Res-0603-100K"))
    )
    (comp (ref "R29")
      (value "10K")
      (footprint "RES 1608-0603")
      (description "RES SMD 10K OHM 1% 1/10W 0603")
      (fields (field (name "PUBLISHER") "Altium Limited"))
      (libsource (lib "RUMBA_v2") (part "Res-0603-10K"))
    )
    (comp (ref "R30")
      (value "100K")
      (footprint "RES 1608-0603")
      (description "RES SMD 100K OHM 1% 1/10W 0603")
      (fields (field (name "PUBLISHER") "Altium Limited"))
      (libsource (lib "RUMBA_v2") (part "Res-0603-100K"))
    )
    (comp (ref "R31")
      (value "22R")
      (footprint "RES 1608-0603")
      (description "RES SMD 22 OHM 1% 1/10W 0603")
      (fields (field (name "PUBLISHER") "Altium Limited"))
      (libsource (lib "RUMBA_v2") (part "Res-0603-22R"))
    )
    (comp (ref "R32")
      (value "100K")
      (footprint "RES 1608-0603")
      (description "RES SMD 100K OHM 1% 1/10W 0603")
      (fields (field (name "PUBLISHER") "Altium Limited"))
      (libsource (lib "RUMBA_v2") (part "Res-0603-100K"))
    )
    (comp (ref "R33")
      (value "1K")
      (footprint "RES 1608-0603")
      (description "RES SMD 1K OHM 1% 1/10W 0603")
      (fields (field (name "PUBLISHER") "Altium Limited"))
      (libsource (lib "RUMBA_v2") (part "Res-0603-1K"))
    )
    (comp (ref "R34")
      (value "22R")
      (footprint "RES 1608-0603")
      (description "RES SMD 22 OHM 1% 1/10W 0603")
      (fields (field (name "PUBLISHER") "Altium Limited"))
      (libsource (lib "RUMBA_v2") (part "Res-0603-22R"))
    )
    (comp (ref "R35")
      (value "100K")
      (footprint "RES 1608-0603")
      (description "RES SMD 100K OHM 1% 1/10W 0603")
      (fields (field (name "PUBLISHER") "Altium Limited"))
      (libsource (lib "RUMBA_v2") (part "Res-0603-100K"))
    )
    (comp (ref "R36")
      (value "1K")
      (footprint "RES 1608-0603")
      (description "RES SMD 1K OHM 1% 1/10W 0603")
      (fields (field (name "PUBLISHER") "Altium Limited"))
      (libsource (lib "RUMBA_v2") (part "Res-0603-1K"))
    )
    (comp (ref "R37")
      (value "22R")
      (footprint "RES 1608-0603")
      (description "RES SMD 22 OHM 1% 1/10W 0603")
      (fields (field (name "PUBLISHER") "Altium Limited"))
      (libsource (lib "RUMBA_v2") (part "Res-0603-22R"))
    )
    (comp (ref "R38")
      (value "100K")
      (footprint "RES 1608-0603")
      (description "RES SMD 100K OHM 1% 1/10W 0603")
      (fields (field (name "PUBLISHER") "Altium Limited"))
      (libsource (lib "RUMBA_v2") (part "Res-0603-100K"))
    )
    (comp (ref "R39")
      (value "1K")
      (footprint "RES 1608-0603")
      (description "RES SMD 1K OHM 1% 1/10W 0603")
      (fields (field (name "PUBLISHER") "Altium Limited"))
      (libsource (lib "RUMBA_v2") (part "Res-0603-1K"))
    )
    (comp (ref "R40")
      (value "4.7K")
      (footprint "RES 1608-0603")
      (description "RES SMD 4.7K OHM 1% 1/10W 0603")
      (fields (field (name "PUBLISHER") "Altium Limited"))
      (libsource (lib "RUMBA_v2") (part "Res-0603-4K7"))
    )
    (comp (ref "R41")
      (value "4.7K")
      (footprint "RES 1608-0603")
      (description "RES SMD 4.7K OHM 1% 1/10W 0603")
      (fields (field (name "PUBLISHER") "Altium Limited"))
      (libsource (lib "RUMBA_v2") (part "Res-0603-4K7"))
    )
    (comp (ref "R42")
      (value "4.7K")
      (footprint "RES 1608-0603")
      (description "RES SMD 4.7K OHM 1% 1/10W 0603")
      (fields (field (name "PUBLISHER") "Altium Limited"))
      (libsource (lib "RUMBA_v2") (part "Res-0603-4K7"))
    )
    (comp (ref "R43")
      (value "4.7K")
      (footprint "RES 1608-0603")
      (description "RES SMD 4.7K OHM 1% 1/10W 0603")
      (fields (field (name "PUBLISHER") "Altium Limited"))
      (libsource (lib "RUMBA_v2") (part "Res-0603-4K7"))
    )
    (comp (ref "R44")
      (value "100K")
      (footprint "RES 1608-0603")
      (description "RES SMD 100K OHM 1% 1/10W 0603")
      (fields (field (name "PUBLISHER") "Altium Limited"))
      (libsource (lib "RUMBA_v2") (part "Res-0603-100K"))
    )
    (comp (ref "R45")
      (value "10K")
      (footprint "RES 1608-0603")
      (description "RES SMD 10K OHM 1% 1/10W 0603")
      (fields (field (name "PUBLISHER") "Altium Limited"))
      (libsource (lib "RUMBA_v2") (part "Res-0603-10K"))
    )
    (comp (ref "R46")
      (value "22R")
      (footprint "RES 1608-0603")
      (description "RES SMD 22 OHM 1% 1/10W 0603")
      (fields (field (name "PUBLISHER") "Altium Limited"))
      (libsource (lib "RUMBA_v2") (part "Res-0603-22R"))
    )
    (comp (ref "R47")
      (value "100K")
      (footprint "RES 1608-0603")
      (description "RES SMD 100K OHM 1% 1/10W 0603")
      (fields (field (name "PUBLISHER") "Altium Limited"))
      (libsource (lib "RUMBA_v2") (part "Res-0603-100K"))
    )
    (comp (ref "R48")
      (value "22R")
      (footprint "RES 1608-0603")
      (description "RES SMD 22 OHM 1% 1/10W 0603")
      (fields (field (name "PUBLISHER") "Altium Limited"))
      (libsource (lib "RUMBA_v2") (part "Res-0603-22R"))
    )
    (comp (ref "R49")
      (value "100K")
      (footprint "RES 1608-0603")
      (description "RES SMD 100K OHM 1% 1/10W 0603")
      (fields (field (name "PUBLISHER") "Altium Limited"))
      (libsource (lib "RUMBA_v2") (part "Res-0603-100K"))
    )
    (comp (ref "R50")
      (value "1K")
      (footprint "RES 1608-0603")
      (description "RES SMD 1K OHM 1% 1/10W 0603")
      (fields (field (name "PUBLISHER") "Altium Limited"))
      (libsource (lib "RUMBA_v2") (part "Res-0603-1K"))
    )
    (comp (ref "R51")
      (value "22R")
      (footprint "RES 1608-0603")
      (description "RES SMD 22 OHM 1% 1/10W 0603")
      (fields (field (name "PUBLISHER") "Altium Limited"))
      (libsource (lib "RUMBA_v2") (part "Res-0603-22R"))
    )
    (comp (ref "R52")
      (value "100K")
      (footprint "RES 1608-0603")
      (description "RES SMD 100K OHM 1% 1/10W 0603")
      (fields (field (name "PUBLISHER") "Altium Limited"))
      (libsource (lib "RUMBA_v2") (part "Res-0603-100K"))
    )
    (comp (ref "R53")
      (value "1K")
      (footprint "RES 1608-0603")
      (description "RES SMD 1K OHM 1% 1/10W 0603")
      (fields (field (name "PUBLISHER") "Altium Limited"))
      (libsource (lib "RUMBA_v2") (part "Res-0603-1K"))
    )
    (comp (ref "R54")
      (value "4.7K")
      (footprint "RES 1608-0603")
      (description "RES SMD 4.7K OHM 1% 1/10W 0603")
      (fields (field (name "PUBLISHER") "Altium Limited"))
      (libsource (lib "RUMBA_v2") (part "Res-0603-4K7"))
    )
    (comp (ref "R55")
      (value "1K")
      (footprint "RES 1608-0603")
      (description "RES SMD 1K OHM 1% 1/10W 0603")
      (fields (field (name "PUBLISHER") "Altium Limited"))
      (libsource (lib "RUMBA_v2") (part "Res-0603-1K"))
    )
    (comp (ref "R56")
      (value "140K")
      (footprint "RES 1608-0603")
      (description "RES SMD 140K OHM 1% 1/10W 0603")
      (fields (field (name "PUBLISHER") "Altium Limited"))
      (libsource (lib "RUMBA_v2") (part "Res-0603-1K"))
    )
    (comp (ref "R57")
      (value "10K")
      (footprint "RES 1608-0603")
      (description "RES SMD 10K OHM 1% 1/10W 0603")
      (fields (field (name "PUBLISHER") "Altium Limited"))
      (libsource (lib "RUMBA_v2") (part "Res-0603-10K"))
    )
    (comp (ref "R58")
      (value "1K")
      (footprint "RES 1608-0603")
      (description "RES SMD 1K OHM 1% 1/10W 0603")
      (fields (field (name "PUBLISHER") "Altium Limited"))
      (libsource (lib "RUMBA_v2") (part "Res-0603-1K"))
    )
    (comp (ref "R59")
      (value "4.7K")
      (footprint "RES 1608-0603")
      (description "RES SMD 4.7K OHM 1% 1/10W 0603")
      (fields (field (name "PUBLISHER") "Altium Limited"))
      (libsource (lib "RUMBA_v2") (part "Res-0603-4K7"))
    )
    (comp (ref "Reset")
      (value "SW-PB")
      (footprint "SW-PB SMD 2pin")
      (description "SWITCH TACTILE SPST-NO 0.05A 12V")
      (libsource (lib "RUMBA_v2") (part "SW-PB"))
    )
    (comp (ref "RX")
      (value "~")
      (footprint "LED 1608-0603")
      (description "LED YELLOW CLEAR CHIP SMD 0603")
      (libsource (lib "picoprint_library") (part "LEDY  0603"))
    )
    (comp (ref "sc1") (value "Sraf") (footprint "Sraf 3mm - rupa 3.2") (libsource (lib "gc") (part "Sraf")))
    (comp (ref "sc2") (value "Sraf") (footprint "Sraf 3mm - rupa 3.2") (libsource (lib "gc") (part "Sraf")))
    (comp (ref "sc3") (value "Sraf") (footprint "Sraf 3mm - rupa 3.5") (libsource (lib "gc") (part "Sraf")))
    (comp (ref "sc4") (value "Sraf") (footprint "Sraf 3mm - rupa 3.5") (libsource (lib "gc") (part "Sraf")))
    (comp (ref "Thermistors")
      (value "Header 5X2")
      (footprint "HDR2X5")
      (description "Header, 5-Pin, Dual row")
      (libsource (lib "") (part "Header 5X2_1"))
    )
    (comp (ref "TX")
      (value "~")
      (footprint "LED 1608-0603")
      (description "LED YELLOW CLEAR CHIP SMD 0603")
      (libsource (lib "picoprint_library") (part "LEDY  0603"))
    )
    (comp (ref "U1")
      (value "ATMEGA2560")
      (footprint "TQFP100N")
      (description "IC MCU 8BIT 256KB FLASH 100TQFP")
      (fields (field (name "SUPPLIER PART NUMBER 1") "ATMEGA2560-16AU-ND"))
      (libsource (lib "RUMBA_v2") (part "ATMEGA2560"))
    )
    (comp (ref "U2")
      (value "ATMEGA16U2-MU")
      (footprint "32M1-A_N")
      (description "IC MCU 8BIT 16KB FLASH 32VQFN")
      (libsource (lib "RUMBA_v2") (part "ATMEGA16U2-MU"))
    )
    (comp (ref "U3")
      (value "~")
      (footprint "SOT23-6N")
      (description "IC REG BUCK ADJ 1.2A SOT23-6")
      (libsource (lib "Schlib1") (part "Buck Regulator AOZ1282CI"))
    )
    (comp (ref "U4")
      (value "AOZ1284")
      (footprint "SOIC127P600X170_HS-9N")
      (description "IC REG BUCK ADJ 4A 8SO")
      (libsource (lib "picoprint_library") (part "Regulator - AOZ1284 4A Buck Regulator"))
    )
    (comp (ref "U5")
      (value "~")
      (footprint "SOT23-6N")
      (description "TVS DIODE 5.25V 17V SOT23-6")
      (libsource (lib "picoprint_library") (part "USBLC6-4SC6 USB ESD Protection"))
    )
    (comp (ref "USB_AUX")
      (value "Header 5")
      (footprint "HDR1X5-HEADER")
      (description "Header, 5-Pin")
      (libsource (lib "picoprint_library") (part "Header 5x1"))
    )
    (comp (ref "VFA0_sel")
      (value "Header 3")
      (footprint "HDR1X3")
      (description "Header, 3-Pin")
      (libsource (lib "RUMBA_v2") (part "Header 3"))
    )
    (comp (ref "VFA1_sel")
      (value "Header 3")
      (footprint "HDR1X3")
      (description "Header, 3-Pin")
      (libsource (lib "RUMBA_v2") (part "Header 3"))
    )
    (comp (ref "VHE2_sel")
      (value "Header 3")
      (footprint "HDR1X3")
      (description "Header, 3-Pin")
      (libsource (lib "RUMBA_v2") (part "Header 3"))
    )
    (comp (ref "X")
      (value "A4988BREAKOUT")
      (footprint "A4988BREAKOUT")
      (libsource (lib "RUMBA_v2") (part "A4988BREAKOUT"))
    )
    (comp (ref "X+")
      (value "Header 3")
      (footprint "HDR1X3")
      (description "Header, 3-Pin")
      (libsource (lib "RUMBA_v2") (part "Header 3"))
    )
    (comp (ref "X-")
      (value "Header 3")
      (footprint "HDR1X3")
      (description "Header, 3-Pin")
      (libsource (lib "RUMBA_v2") (part "Header 3"))
    )
    (comp (ref "X_1")
      (value "~")
      (footprint "HDR1X8-HEADER")
      (description "Header, 8-Pin, Female")
      (libsource (lib "picoprint_library") (part "Header 8x1"))
    )
    (comp (ref "X_2")
      (value "~")
      (footprint "HDR1X8-HEADER")
      (description "Header, 8-Pin, Female")
      (libsource (lib "picoprint_library") (part "Header 8x1"))
    )
    (comp (ref "X_MOT")
      (value "~")
      (footprint "TERM4 3.5mm")
      (description "TERM BLK 4POS SIDE ENT 3.5MM PCB")
      (fields (field (name "PUBLISHER") "Altium Limited"))
      (libsource (lib "RUMBA_v2") (part "ScrewTerminal-3.5mm-4Way"))
    )
    (comp (ref "X_MOT_A")
      (value "Header 4")
      (footprint "HDR1X4")
      (description "Header, 4-Pin")
      (libsource (lib "RUMBA_v2") (part "Header 4_1"))
    )
    (comp (ref "X_MS")
      (value "SW DIP-3")
      (footprint "dipsw SO6")
      (description "SWITCH SLIDE DIP SPST 25MA 24V")
      (fields (field (name "PUBLISHER") "Altium Limited"))
      (libsource (lib "RUMBA_v2") (part "SW DIP-3"))
    )
    (comp (ref "Y")
      (value "A4988BREAKOUT")
      (footprint "A4988BREAKOUT")
      (libsource (lib "RUMBA_v2") (part "A4988BREAKOUT"))
    )
    (comp (ref "Y+")
      (value "Header 3")
      (footprint "HDR1X3")
      (description "Header, 3-Pin")
      (libsource (lib "RUMBA_v2") (part "Header 3"))
    )
    (comp (ref "Y-")
      (value "Header 3")
      (footprint "HDR1X3")
      (description "Header, 3-Pin")
      (libsource (lib "RUMBA_v2") (part "Header 3"))
    )
    (comp (ref "Y1")
      (value "16MHz")
      (footprint "3525 SMD Crystal")
      (description "CRYSTAL 16.0000MHZ 18PF SMD")
      (libsource (lib "RUMBA_v2") (part "XTAL_2"))
    )
    (comp (ref "Y2")
      (value "16MHz")
      (footprint "3525 SMD Crystal")
      (description "CRYSTAL 16.0000MHZ 18PF SMD")
      (libsource (lib "RUMBA_v2") (part "XTAL_2"))
    )
    (comp (ref "Y_0")
      (value "~")
      (footprint "HDR1X8-HEADER")
      (description "Header, 8-Pin, Female")
      (libsource (lib "picoprint_library") (part "Header 8x1"))
    )
    (comp (ref "Y_1")
      (value "~")
      (footprint "HDR1X8-HEADER")
      (description "Header, 8-Pin, Female")
      (libsource (lib "picoprint_library") (part "Header 8x1"))
    )
    (comp (ref "Y_MOT")
      (value "~")
      (footprint "TERM4 3.5mm")
      (description "TERM BLK 4POS SIDE ENT 3.5MM PCB")
      (fields (field (name "PUBLISHER") "Altium Limited"))
      (libsource (lib "RUMBA_v2") (part "ScrewTerminal-3.5mm-4Way"))
    )
    (comp (ref "Y_MOT_A")
      (value "Header 4")
      (footprint "HDR1X4")
      (description "Header, 4-Pin")
      (libsource (lib "RUMBA_v2") (part "Header 4_1"))
    )
    (comp (ref "Y_MS")
      (value "SW DIP-3")
      (footprint "dipsw SO6")
      (description "SWITCH SLIDE DIP SPST 25MA 24V")
      (fields (field (name "PUBLISHER") "Altium Limited"))
      (libsource (lib "RUMBA_v2") (part "SW DIP-3"))
    )
    (comp (ref "Z")
      (value "A4988BREAKOUT")
      (footprint "A4988BREAKOUT")
      (libsource (lib "RUMBA_v2") (part "A4988BREAKOUT"))
    )
    (comp (ref "Z+")
      (value "Header 3")
      (footprint "HDR1X3")
      (description "Header, 3-Pin")
      (libsource (lib "RUMBA_v2") (part "Header 3"))
    )
    (comp (ref "Z-")
      (value "Header 3")
      (footprint "HDR1X3")
      (description "Header, 3-Pin")
      (libsource (lib "RUMBA_v2") (part "Header 3"))
    )
    (comp (ref "Z_0")
      (value "~")
      (footprint "HDR1X8-HEADER")
      (description "Header, 8-Pin, Female")
      (libsource (lib "picoprint_library") (part "Header 8x1"))
    )
    (comp (ref "Z_1")
      (value "~")
      (footprint "HDR1X8-HEADER")
      (description "Header, 8-Pin, Female")
      (libsource (lib "picoprint_library") (part "Header 8x1"))
    )
    (comp (ref "Z_MOT")
      (value "~")
      (footprint "TERM4 3.5mm")
      (description "TERM BLK 4POS SIDE ENT 3.5MM PCB")
      (fields (field (name "PUBLISHER") "Altium Limited"))
      (libsource (lib "RUMBA_v2") (part "ScrewTerminal-3.5mm-4Way"))
    )
    (comp (ref "Z_MOT_A")
      (value "Header 4")
      (footprint "HDR1X4")
      (description "Header, 4-Pin")
      (libsource (lib "RUMBA_v2") (part "Header 4_1"))
    )
    (comp (ref "Z_MS")
      (value "SW DIP-3")
      (footprint "dipsw SO6")
      (description "SWITCH SLIDE DIP SPST 25MA 24V")
      (fields (field (name "PUBLISHER") "Altium Limited"))
      (libsource (lib "RUMBA_v2") (part "SW DIP-3"))
    )
  )
  (nets
    (net (code "1") (name "+5V") (class "Default")
      (node (ref "5V") (pin "1") (pinfunction "1_1") (pintype "passive"))
      (node (ref "C13") (pin "2") (pinfunction "2_2") (pintype "passive"))
      (node (ref "C35") (pin "2") (pinfunction "2_2") (pintype "passive"))
      (node (ref "C5") (pin "2") (pinfunction "2_2") (pintype "passive"))
      (node (ref "C6") (pin "2") (pinfunction "2_2") (pintype "passive"))
      (node (ref "C7") (pin "2") (pinfunction "2_2") (pintype "passive"))
      (node (ref "D15") (pin "K") (pinfunction "K_K") (pintype "passive"))
      (node (ref "D2") (pin "K") (pinfunction "K_K") (pintype "passive"))
      (node (ref "D3") (pin "K") (pinfunction "K_K") (pintype "passive"))
      (node (ref "D4") (pin "K") (pinfunction "K_K") (pintype "passive"))
      (node (ref "ENC_1") (pin "4") (pinfunction "4_4") (pintype "passive"))
      (node (ref "ENC_2") (pin "4") (pinfunction "4_4") (pintype "passive"))
      (node (ref "ENC_3") (pin "4") (pinfunction "4_4") (pintype "passive"))
      (node (ref "ENC_4") (pin "4") (pinfunction "4_4") (pintype "passive"))
      (node (ref "EXP1") (pin "10") (pinfunction "10_10") (pintype "passive"))
      (node (ref "EXP3") (pin "2") (pinfunction "2_2") (pintype "passive"))
      (node (ref "ISP1") (pin "2") (pinfunction "2_2") (pintype "passive"))
      (node (ref "ISP2") (pin "2") (pinfunction "2_2") (pintype "passive"))
      (node (ref "JTAG") (pin "4") (pinfunction "4_4") (pintype "passive"))
      (node (ref "JTAG") (pin "7") (pinfunction "7_7") (pintype "passive"))
      (node (ref "R11") (pin "2") (pinfunction "2_2") (pintype "passive"))
      (node (ref "R12") (pin "2") (pinfunction "2_2") (pintype "passive"))
      (node (ref "R15") (pin "1") (pinfunction "1_1") (pintype "passive"))
      (node (ref "R16") (pin "1") (pinfunction "1_1") (pintype "passive"))
      (node (ref "R2") (pin "2") (pinfunction "2_2") (pintype "passive"))
      (node (ref "R3") (pin "2") (pinfunction "2_2") (pintype "passive"))
      (node (ref "R40") (pin "1") (pinfunction "1_1") (pintype "passive"))
      (node (ref "R41") (pin "1") (pinfunction "1_1") (pintype "passive"))
      (node (ref "R42") (pin "1") (pinfunction "1_1") (pintype "passive"))
      (node (ref "R43") (pin "1") (pinfunction "1_1") (pintype "passive"))
      (node (ref "R54") (pin "1") (pinfunction "1_1") (pintype "passive"))
      (node (ref "R58") (pin "2") (pinfunction "2_2") (pintype "passive"))
      (node (ref "U1") (pin "10") (pinfunction "VCC_10") (pintype "passive"))
      (node (ref "U1") (pin "100") (pinfunction "AVCC_100") (pintype "passive"))
      (node (ref "U1") (pin "31") (pinfunction "VCC_31") (pintype "passive"))
      (node (ref "U1") (pin "61") (pinfunction "VCC_61") (pintype "passive"))
      (node (ref "U1") (pin "80") (pinfunction "VCC_80") (pintype "passive"))
      (node (ref "U2") (pin "32") (pinfunction "AVCC_32") (pintype "passive"))
      (node (ref "U2") (pin "4") (pinfunction "VCC_4") (pintype "passive"))
      (node (ref "X+") (pin "3") (pinfunction "3_3") (pintype "passive"))
      (node (ref "X-") (pin "3") (pinfunction "3_3") (pintype "passive"))
      (node (ref "Y+") (pin "3") (pinfunction "3_3") (pintype "passive"))
      (node (ref "Y-") (pin "3") (pinfunction "3_3") (pintype "passive"))
      (node (ref "Z+") (pin "3") (pinfunction "3_3") (pintype "passive"))
      (node (ref "Z-") (pin "3") (pinfunction "3_3") (pintype "passive"))
    )
    (net (code "2") (name "+12V") (class "Default")
      (node (ref "12V") (pin "1") (pinfunction "1_1") (pintype "passive"))
      (node (ref "C32") (pin "1") (pinfunction "1_1") (pintype "passive"))
      (node (ref "C36") (pin "2") (pinfunction "2_2") (pintype "passive"))
      (node (ref "EXP3") (pin "1") (pinfunction "1_1") (pintype "passive"))
      (node (ref "L4") (pin "2") (pinfunction "2_2") (pintype "passive"))
      (node (ref "R56") (pin "1") (pinfunction "1_1") (pintype "passive"))
      (node (ref "R59") (pin "2") (pinfunction "2_2") (pintype "passive"))
      (node (ref "VFA0_sel") (pin "3") (pinfunction "3_3") (pintype "passive"))
      (node (ref "VFA1_sel") (pin "3") (pinfunction "3_3") (pintype "passive"))
      (node (ref "VHE2_sel") (pin "3") (pinfunction "3_3") (pintype "passive"))
    )
    (net (code "3") (name "/A9") (class "Default")
      (node (ref "EXP3") (pin "7") (pinfunction "7_7") (pintype "passive"))
      (node (ref "U1") (pin "88") (pinfunction "PK1(ADC9/PCINT17)_88") (pintype "passive"))
    )
    (net (code "4") (name "/A10") (class "Default")
      (node (ref "EXP3") (pin "8") (pinfunction "8_8") (pintype "passive"))
      (node (ref "U1") (pin "87") (pinfunction "PK2(ADC10/PCINT18)_87") (pintype "passive"))
    )
    (net (code "5") (name "/AREF") (class "Default")
      (node (ref "C4") (pin "2") (pinfunction "2_2") (pintype "passive"))
      (node (ref "U1") (pin "98") (pinfunction "AREF_98") (pintype "passive"))
    )
    (net (code "6") (name "/BEEPER") (class "Default")
      (node (ref "EXP1") (pin "1") (pinfunction "1_1") (pintype "passive"))
      (node (ref "U1") (pin "40") (pinfunction "PL5(OC5C)_40") (pintype "passive"))
    )
    (net (code "7") (name "/BTN_EN1") (class "Default")
      (node (ref "EXP2") (pin "5") (pinfunction "5_5") (pintype "passive"))
      (node (ref "U1") (pin "25") (pinfunction "(OC1B/PCINT6)PB6_25") (pintype "passive"))
    )
    (net (code "8") (name "/BTN_EN2") (class "Default")
      (node (ref "EXP2") (pin "3") (pinfunction "3_3") (pintype "passive"))
      (node (ref "U1") (pin "24") (pinfunction "(OC1A/PCINT5)PB5_24") (pintype "passive"))
    )
    (net (code "9") (name "/BTN_ENC") (class "Default")
      (node (ref "EXP1") (pin "2") (pinfunction "2_2") (pintype "passive"))
      (node (ref "U1") (pin "41") (pinfunction "PL6_41") (pintype "passive"))
    )
    (net (code "10") (name "/DTR") (class "Default")
      (node (ref "C16") (pin "2") (pinfunction "2_2") (pintype "passive"))
      (node (ref "R14") (pin "1") (pinfunction "1_1") (pintype "passive"))
      (node (ref "U2") (pin "13") (pinfunction "(CTS/HWB/AIN6/TO/INT7)PD7_13") (pintype "passive"))
    )
    (net (code "11") (name "/E0-DIR") (class "Default")
      (node (ref "E0") (pin "8") (pinfunction "DIR_8") (pintype "passive"))
      (node (ref "U1") (pin "78") (pinfunction "(AD0)PA0_78") (pintype "passive"))
    )
    (net (code "12") (name "/E0-EN") (class "Default")
      (node (ref "E0") (pin "1") (pinfunction "~{ENA}_1") (pintype "passive"))
      (node (ref "R27") (pin "2") (pinfunction "2_2") (pintype "passive"))
      (node (ref "U1") (pin "76") (pinfunction "(AD2)PA2_76") (pintype "passive"))
    )
    (net (code "13") (name "/E0-STEP") (class "Default")
      (node (ref "E0") (pin "7") (pinfunction "STEP_7") (pintype "passive"))
      (node (ref "U1") (pin "77") (pinfunction "(AD1)PA1_77") (pintype "passive"))
    )
    (net (code "14") (name "/E1-DIR") (class "Default")
      (node (ref "E1") (pin "8") (pinfunction "DIR_8") (pintype "passive"))
      (node (ref "U1") (pin "75") (pinfunction "(AD3)PA3_75") (pintype "passive"))
    )
    (net (code "15") (name "/E1-EN") (class "Default")
      (node (ref "E1") (pin "1") (pinfunction "~{ENA}_1") (pintype "passive"))
      (node (ref "R29") (pin "2") (pinfunction "2_2") (pintype "passive"))
      (node (ref "U1") (pin "73") (pinfunction "(AD5)PA5_73") (pintype "passive"))
    )
    (net (code "16") (name "/E1-STEP") (class "Default")
      (node (ref "E1") (pin "7") (pinfunction "STEP_7") (pintype "passive"))
      (node (ref "U1") (pin "74") (pinfunction "(AD4)PA4_74") (pintype "passive"))
    )
    (net (code "17") (name "/E2-DIR") (class "Default")
      (node (ref "E2") (pin "8") (pinfunction "DIR_8") (pintype "passive"))
      (node (ref "U1") (pin "72") (pinfunction "(AD6)PA6_72") (pintype "passive"))
    )
    (net (code "18") (name "/E2-EN") (class "Default")
      (node (ref "E2") (pin "1") (pinfunction "~{ENA}_1") (pintype "passive"))
      (node (ref "R45") (pin "2") (pinfunction "2_2") (pintype "passive"))
      (node (ref "U1") (pin "70") (pinfunction "(ALE)PG2_70") (pintype "passive"))
    )
    (net (code "19") (name "/E2-STEP") (class "Default")
      (node (ref "E2") (pin "7") (pinfunction "STEP_7") (pintype "passive"))
      (node (ref "U1") (pin "71") (pinfunction "(AD7)PA7_71") (pintype "passive"))
    )
    (net (code "20") (name "/FAN_0") (class "Default")
      (node (ref "R46") (pin "1") (pinfunction "1_1") (pintype "passive"))
      (node (ref "R47") (pin "1") (pinfunction "1_1") (pintype "passive"))
      (node (ref "R55") (pin "2") (pinfunction "2_2") (pintype "passive"))
      (node (ref "U1") (pin "17") (pinfunction "PH5(OC4C)_17") (pintype "passive"))
    )
    (net (code "21") (name "/FAN_1") (class "Default")
      (node (ref "R51") (pin "1") (pinfunction "1_1") (pintype "passive"))
      (node (ref "R52") (pin "1") (pinfunction "1_1") (pintype "passive"))
      (node (ref "R53") (pin "2") (pinfunction "2_2") (pintype "passive"))
      (node (ref "U1") (pin "16") (pinfunction "PH4(OC4B)_16") (pintype "passive"))
    )
    (net (code "22") (name "/FB1") (class "Default")
      (node (ref "R5") (pin "1") (pinfunction "1_1") (pintype "passive"))
      (node (ref "R6") (pin "2") (pinfunction "2_2") (pintype "passive"))
      (node (ref "U3") (pin "3") (pinfunction "FB_3") (pintype "passive"))
    )
    (net (code "23") (name "/FB2") (class "Default")
      (node (ref "R56") (pin "2") (pinfunction "2_2") (pintype "passive"))
      (node (ref "R57") (pin "2") (pinfunction "2_2") (pintype "passive"))
      (node (ref "U4") (pin "6") (pinfunction "FB_6") (pintype "passive"))
    )
    (net (code "24") (name "/HB") (class "Default")
      (node (ref "R31") (pin "1") (pinfunction "1_1") (pintype "passive"))
      (node (ref "R32") (pin "1") (pinfunction "1_1") (pintype "passive"))
      (node (ref "R33") (pin "2") (pinfunction "2_2") (pintype "passive"))
      (node (ref "U1") (pin "18") (pinfunction "PH6(OC2B)_18") (pintype "passive"))
    )
    (net (code "25") (name "/HE_0") (class "Default")
      (node (ref "R34") (pin "1") (pinfunction "1_1") (pintype "passive"))
      (node (ref "R35") (pin "1") (pinfunction "1_1") (pintype "passive"))
      (node (ref "R36") (pin "2") (pinfunction "2_2") (pintype "passive"))
      (node (ref "U1") (pin "6") (pinfunction "(OC3B/INT4)PE4_6") (pintype "passive"))
    )
    (net (code "26") (name "/HE_1") (class "Default")
      (node (ref "R37") (pin "1") (pinfunction "1_1") (pintype "passive"))
      (node (ref "R38") (pin "1") (pinfunction "1_1") (pintype "passive"))
      (node (ref "R39") (pin "2") (pinfunction "2_2") (pintype "passive"))
      (node (ref "U1") (pin "7") (pinfunction "(OC3C/INT5)PE5_7") (pintype "passive"))
    )
    (net (code "27") (name "/HE_2") (class "Default")
      (node (ref "R48") (pin "1") (pinfunction "1_1") (pintype "passive"))
      (node (ref "R49") (pin "1") (pinfunction "1_1") (pintype "passive"))
      (node (ref "R50") (pin "2") (pinfunction "2_2") (pintype "passive"))
      (node (ref "U1") (pin "15") (pinfunction "PH3(OC4A)_15") (pintype "passive"))
    )
    (net (code "28") (name "/J_TCK") (class "Default")
      (node (ref "JTAG") (pin "1") (pinfunction "1_1") (pintype "passive"))
      (node (ref "U1") (pin "93") (pinfunction "(ADC4/TCK)PF4_93") (pintype "passive"))
    )
    (net (code "29") (name "/J_TDI") (class "Default")
      (node (ref "JTAG") (pin "9") (pinfunction "9_9") (pintype "passive"))
      (node (ref "U1") (pin "90") (pinfunction "(ADC7/TDI)PF7_90") (pintype "passive"))
    )
    (net (code "30") (name "/J_TDO") (class "Default")
      (node (ref "JTAG") (pin "3") (pinfunction "3_3") (pintype "passive"))
      (node (ref "U1") (pin "91") (pinfunction "(ADC6/TDO)PF6_91") (pintype "passive"))
    )
    (net (code "31") (name "/J_TMS") (class "Default")
      (node (ref "JTAG") (pin "5") (pinfunction "5_5") (pintype "passive"))
      (node (ref "U1") (pin "92") (pinfunction "(ADC5/TMS)PF5_92") (pintype "passive"))
    )
    (net (code "32") (name "/KILL") (class "Default")
      (node (ref "EXP2") (pin "10") (pinfunction "10_10") (pintype "passive"))
      (node (ref "U1") (pin "38") (pinfunction "PL3(OC5A)_38") (pintype "passive"))
    )
    (net (code "33") (name "/LCD_D4") (class "Default")
      (node (ref "EXP1") (pin "5") (pinfunction "5_5") (pintype "passive"))
      (node (ref "U1") (pin "46") (pinfunction "(TXD1/INT3)PD3_46") (pintype "passive"))
    )
    (net (code "34") (name "/LCD_D5") (class "Default")
      (node (ref "EXP1") (pin "6") (pinfunction "6_6") (pintype "passive"))
      (node (ref "U1") (pin "50") (pinfunction "(T0)PD7_50") (pintype "passive"))
    )
    (net (code "35") (name "/LCD_D6") (class "Default")
      (node (ref "EXP1") (pin "7") (pinfunction "7_7") (pintype "passive"))
      (node (ref "U1") (pin "51") (pinfunction "(WR)PG0_51") (pintype "passive"))
    )
    (net (code "36") (name "/LCD_D7") (class "Default")
      (node (ref "EXP1") (pin "8") (pinfunction "8_8") (pintype "passive"))
      (node (ref "U1") (pin "52") (pinfunction "(RD)PG1_52") (pintype "passive"))
    )
    (net (code "37") (name "/LCD_ENA") (class "Default")
      (node (ref "EXP1") (pin "3") (pinfunction "3_3") (pintype "passive"))
      (node (ref "U1") (pin "42") (pinfunction "PL7_42") (pintype "passive"))
    )
    (net (code "38") (name "/LCD_RS") (class "Default")
      (node (ref "EXP1") (pin "4") (pinfunction "4_4") (pintype "passive"))
      (node (ref "U1") (pin "45") (pinfunction "(RXD1/INT2)PD2_45") (pintype "passive"))
    )
    (net (code "39") (name "/LED") (class "Default")
      (node (ref "R13") (pin "2") (pinfunction "2_2") (pintype "passive"))
      (node (ref "U1") (pin "26") (pinfunction "(OC0A/OC1C/PCINT7)PB7_26") (pintype "passive"))
    )
    (net (code "40") (name "/MISO2") (class "Default")
      (node (ref "ISP2") (pin "1") (pinfunction "1_1") (pintype "passive"))
      (node (ref "U2") (pin "17") (pinfunction "(PD0/MISO/PCINT3)PB3_17") (pintype "passive"))
    )
    (net (code "41") (name "/MOSI2") (class "Default")
      (node (ref "ISP2") (pin "4") (pinfunction "4_4") (pintype "passive"))
      (node (ref "U2") (pin "16") (pinfunction "(PDI/MOSI/PCINT2)PB2_16") (pintype "passive"))
    )
    (net (code "42") (name "/PB1_(SCK)") (class "Default")
      (node (ref "EXP2") (pin "2") (pinfunction "2_2") (pintype "passive"))
      (node (ref "ISP1") (pin "3") (pinfunction "3_3") (pintype "passive"))
      (node (ref "U1") (pin "20") (pinfunction "(SCK/PCINT1)PB1_20") (pintype "passive"))
    )
    (net (code "43") (name "/PB2_(MOSI)") (class "Default")
      (node (ref "EXP2") (pin "6") (pinfunction "6_6") (pintype "passive"))
      (node (ref "ISP1") (pin "4") (pinfunction "4_4") (pintype "passive"))
      (node (ref "U1") (pin "21") (pinfunction "(MOSI/PCINT2)PB2_21") (pintype "passive"))
    )
    (net (code "44") (name "/PB3_(MISO)") (class "Default")
      (node (ref "EXP2") (pin "1") (pinfunction "1_1") (pintype "passive"))
      (node (ref "ISP1") (pin "1") (pinfunction "1_1") (pintype "passive"))
      (node (ref "U1") (pin "22") (pinfunction "(MISO/PCINT3)PB3_22") (pintype "passive"))
    )
    (net (code "45") (name "/PC6") (class "Default")
      (node (ref "EXP3") (pin "14") (pinfunction "14_14") (pintype "passive"))
      (node (ref "U1") (pin "59") (pinfunction "(A14)PC6_59") (pintype "passive"))
    )
    (net (code "46") (name "/PC7") (class "Default")
      (node (ref "EXP3") (pin "13") (pinfunction "13_13") (pintype "passive"))
      (node (ref "U1") (pin "60") (pinfunction "(A15)PC7_60") (pintype "passive"))
    )
    (net (code "47") (name "/PJ0") (class "Default")
      (node (ref "EXP3") (pin "12") (pinfunction "12_12") (pintype "passive"))
      (node (ref "U1") (pin "63") (pinfunction "PJ0(RXD3/PCINT9)_63") (pintype "passive"))
    )
    (net (code "48") (name "/PJ1") (class "Default")
      (node (ref "EXP3") (pin "11") (pinfunction "11_11") (pintype "passive"))
      (node (ref "U1") (pin "64") (pinfunction "PJ1(TXD3/PCINT10)_64") (pintype "passive"))
    )
    (net (code "49") (name "/PS_ON") (class "Default")
      (node (ref "PS_ON") (pin "1") (pinfunction "1_1") (pintype "passive"))
      (node (ref "U1") (pin "39") (pinfunction "PL4(OC5B)_39") (pintype "passive"))
    )
    (net (code "50") (name "/PWM_1") (class "Default")
      (node (ref "EXP3") (pin "5") (pinfunction "5_5") (pintype "passive"))
      (node (ref "U1") (pin "1") (pinfunction "(OC0B)PG5_1") (pintype "passive"))
    )
    (net (code "51") (name "/PWM_2") (class "Default")
      (node (ref "EXP3") (pin "6") (pinfunction "6_6") (pintype "passive"))
      (node (ref "U1") (pin "5") (pinfunction "(OC3A/AIN1)PE3_5") (pintype "passive"))
    )
    (net (code "52") (name "/RESET") (class "Default")
      (node (ref "C16") (pin "1") (pinfunction "1_1") (pintype "passive"))
      (node (ref "C8") (pin "2") (pinfunction "2_2") (pintype "passive"))
      (node (ref "D2") (pin "A") (pinfunction "A_A") (pintype "passive"))
      (node (ref "EXP2") (pin "8") (pinfunction "8_8") (pintype "passive"))
      (node (ref "ISP1") (pin "5") (pinfunction "5_5") (pintype "passive"))
      (node (ref "JTAG") (pin "6") (pinfunction "6_6") (pintype "passive"))
      (node (ref "R11") (pin "1") (pinfunction "1_1") (pintype "passive"))
      (node (ref "Reset") (pin "2") (pintype "passive"))
      (node (ref "U1") (pin "30") (pinfunction "~{RESET}_30") (pintype "passive"))
    )
    (net (code "53") (name "/RESET2") (class "Default")
      (node (ref "D3") (pin "A") (pinfunction "A_A") (pintype "passive"))
      (node (ref "ISP2") (pin "5") (pinfunction "5_5") (pintype "passive"))
      (node (ref "R12") (pin "1") (pinfunction "1_1") (pintype "passive"))
      (node (ref "U2") (pin "24") (pinfunction "RESET(PC1/DW)_24") (pintype "passive"))
    )
    (net (code "54") (name "/SCK2") (class "Default")
      (node (ref "ISP2") (pin "3") (pinfunction "3_3") (pintype "passive"))
      (node (ref "U2") (pin "15") (pinfunction "(SCLK/PCINT1)PB1_15") (pintype "passive"))
    )
    (net (code "55") (name "/SCL") (class "Default")
      (node (ref "ENC_1") (pin "1") (pinfunction "1_1") (pintype "passive"))
      (node (ref "ENC_2") (pin "1") (pinfunction "1_1") (pintype "passive"))
      (node (ref "ENC_3") (pin "1") (pinfunction "1_1") (pintype "passive"))
      (node (ref "ENC_4") (pin "1") (pinfunction "1_1") (pintype "passive"))
      (node (ref "EXP3") (pin "9") (pinfunction "9_9") (pintype "passive"))
      (node (ref "R3") (pin "1") (pinfunction "1_1") (pintype "passive"))
      (node (ref "U1") (pin "43") (pinfunction "(SCL/INT0)PD0_43") (pintype "passive"))
    )
    (net (code "56") (name "/SDA") (class "Default")
      (node (ref "ENC_1") (pin "2") (pinfunction "2_2") (pintype "passive"))
      (node (ref "ENC_2") (pin "2") (pinfunction "2_2") (pintype "passive"))
      (node (ref "ENC_3") (pin "2") (pinfunction "2_2") (pintype "passive"))
      (node (ref "ENC_4") (pin "2") (pinfunction "2_2") (pintype "passive"))
      (node (ref "EXP3") (pin "10") (pinfunction "10_10") (pintype "passive"))
      (node (ref "R2") (pin "1") (pinfunction "1_1") (pintype "passive"))
      (node (ref "U1") (pin "44") (pinfunction "(SDA/INT1)PD1_44") (pintype "passive"))
    )
    (net (code "57") (name "/SD_CSEL") (class "Default")
      (node (ref "EXP2") (pin "4") (pinfunction "4_4") (pintype "passive"))
      (node (ref "U1") (pin "19") (pinfunction "(SS/PCINT0)PB0_19") (pintype "passive"))
    )
    (net (code "58") (name "/SD_DET") (class "Default")
      (node (ref "EXP2") (pin "7") (pinfunction "7_7") (pintype "passive"))
      (node (ref "U1") (pin "35") (pinfunction "PL0(ICP4)_35") (pintype "passive"))
    )
    (net (code "59") (name "/THERM0") (class "Default")
      (node (ref "C29") (pin "1") (pinfunction "1_1") (pintype "passive"))
      (node (ref "R43") (pin "2") (pinfunction "2_2") (pintype "passive"))
      (node (ref "Thermistors") (pin "2") (pinfunction "2_2") (pintype "passive"))
      (node (ref "U1") (pin "82") (pinfunction "PK7(ADC15/PCINT23)_82") (pintype "passive"))
    )
    (net (code "60") (name "/THERM1") (class "Default")
      (node (ref "C28") (pin "1") (pinfunction "1_1") (pintype "passive"))
      (node (ref "R42") (pin "2") (pinfunction "2_2") (pintype "passive"))
      (node (ref "Thermistors") (pin "4") (pinfunction "4_4") (pintype "passive"))
      (node (ref "U1") (pin "83") (pinfunction "PK6(ADC14/PCINT22)_83") (pintype "passive"))
    )
    (net (code "61") (name "/THERM2") (class "Default")
      (node (ref "C27") (pin "1") (pinfunction "1_1") (pintype "passive"))
      (node (ref "R41") (pin "2") (pinfunction "2_2") (pintype "passive"))
      (node (ref "Thermistors") (pin "6") (pinfunction "6_6") (pintype "passive"))
      (node (ref "U1") (pin "84") (pinfunction "PK5(ADC13/PCINT21)_84") (pintype "passive"))
    )
    (net (code "62") (name "/THERM3") (class "Default")
      (node (ref "C26") (pin "1") (pinfunction "1_1") (pintype "passive"))
      (node (ref "R40") (pin "2") (pinfunction "2_2") (pintype "passive"))
      (node (ref "Thermistors") (pin "8") (pinfunction "8_8") (pintype "passive"))
      (node (ref "U1") (pin "85") (pinfunction "PK4(ADC12/PCINT20)_85") (pintype "passive"))
    )
    (net (code "63") (name "/THERM4") (class "Default")
      (node (ref "C9") (pin "1") (pinfunction "1_1") (pintype "passive"))
      (node (ref "R54") (pin "2") (pinfunction "2_2") (pintype "passive"))
      (node (ref "Thermistors") (pin "10") (pinfunction "10_10") (pintype "passive"))
      (node (ref "U1") (pin "86") (pinfunction "PK3(ADC11/PCINT19)_86") (pintype "passive"))
    )
    (net (code "64") (name "/USB RXD") (class "Default")
      (node (ref "R18") (pin "2") (pinfunction "2_2") (pintype "passive"))
      (node (ref "U1") (pin "2") (pinfunction "(RXD0/PCIN8)PE0_2") (pintype "passive"))
    )
    (net (code "65") (name "/USB_TXD") (class "Default")
      (node (ref "R17") (pin "2") (pinfunction "2_2") (pintype "passive"))
      (node (ref "U1") (pin "3") (pinfunction "(TXD0)PE1_3") (pintype "passive"))
    )
    (net (code "66") (name "/USB_XCK") (class "Default")
      (node (ref "U1") (pin "4") (pinfunction "(XCK0/AIN0)PE2_4") (pintype "passive"))
    )
    (net (code "67") (name "/X-DIR") (class "Default")
      (node (ref "U1") (pin "13") (pinfunction "PH1(TXD2)_13") (pintype "passive"))
      (node (ref "X") (pin "8") (pinfunction "DIR_8") (pintype "passive"))
    )
    (net (code "68") (name "/X-EN") (class "Default")
      (node (ref "R21") (pin "2") (pinfunction "2_2") (pintype "passive"))
      (node (ref "U1") (pin "36") (pinfunction "PL1(ICP5)_36") (pintype "passive"))
      (node (ref "X") (pin "1") (pinfunction "~{ENA}_1") (pintype "passive"))
    )
    (net (code "69") (name "/X-MAX") (class "Default")
      (node (ref "U1") (pin "54") (pinfunction "(A9)PC1_54") (pintype "passive"))
      (node (ref "X+") (pin "1") (pinfunction "1_1") (pintype "passive"))
    )
    (net (code "70") (name "/X-MIN") (class "Default")
      (node (ref "U1") (pin "53") (pinfunction "(A8)PC0_53") (pintype "passive"))
      (node (ref "X-") (pin "1") (pinfunction "1_1") (pintype "passive"))
    )
    (net (code "71") (name "/X-STEP") (class "Default")
      (node (ref "U1") (pin "12") (pinfunction "PH0(RXD2)_12") (pintype "passive"))
      (node (ref "X") (pin "7") (pinfunction "STEP_7") (pintype "passive"))
    )
    (net (code "72") (name "/Y-DIR") (class "Default")
      (node (ref "U1") (pin "37") (pinfunction "PL2(T5)_37") (pintype "passive"))
      (node (ref "Y") (pin "8") (pinfunction "DIR_8") (pintype "passive"))
    )
    (net (code "73") (name "/Y-EN") (class "Default")
      (node (ref "R23") (pin "2") (pinfunction "2_2") (pintype "passive"))
      (node (ref "U1") (pin "96") (pinfunction "(ADC1)PF1_96") (pintype "passive"))
      (node (ref "Y") (pin "1") (pinfunction "~{ENA}_1") (pintype "passive"))
    )
    (net (code "74") (name "/Y-MAX") (class "Default")
      (node (ref "U1") (pin "56") (pinfunction "(A11)PC3_56") (pintype "passive"))
      (node (ref "Y+") (pin "1") (pinfunction "1_1") (pintype "passive"))
    )
    (net (code "75") (name "/Y-MIN") (class "Default")
      (node (ref "U1") (pin "55") (pinfunction "(A10)PC2_55") (pintype "passive"))
      (node (ref "Y-") (pin "1") (pinfunction "1_1") (pintype "passive"))
    )
    (net (code "76") (name "/Y-STEP") (class "Default")
      (node (ref "U1") (pin "97") (pinfunction "(ADC0)PF0_97") (pintype "passive"))
      (node (ref "Y") (pin "7") (pinfunction "STEP_7") (pintype "passive"))
    )
    (net (code "77") (name "/Z-DIR") (class "Default")
      (node (ref "U1") (pin "95") (pinfunction "(ADC2)PF2_95") (pintype "passive"))
      (node (ref "Z") (pin "8") (pinfunction "DIR_8") (pintype "passive"))
    )
    (net (code "78") (name "/Z-EN") (class "Default")
      (node (ref "R25") (pin "2") (pinfunction "2_2") (pintype "passive"))
      (node (ref "U1") (pin "89") (pinfunction "PK0(ADC8/PCINT16)_89") (pintype "passive"))
      (node (ref "Z") (pin "1") (pinfunction "~{ENA}_1") (pintype "passive"))
    )
    (net (code "79") (name "/Z-MAX") (class "Default")
      (node (ref "U1") (pin "58") (pinfunction "(A13)PC5_58") (pintype "passive"))
      (node (ref "Z+") (pin "1") (pinfunction "1_1") (pintype "passive"))
    )
    (net (code "80") (name "/Z-MIN") (class "Default")
      (node (ref "U1") (pin "57") (pinfunction "(A12)PC4_57") (pintype "passive"))
      (node (ref "Z-") (pin "1") (pinfunction "1_1") (pintype "passive"))
    )
    (net (code "81") (name "/Z-STEP") (class "Default")
      (node (ref "U1") (pin "94") (pinfunction "(ADC3)PF3_94") (pintype "passive"))
      (node (ref "Z") (pin "7") (pinfunction "STEP_7") (pintype "passive"))
    )
    (net (code "82") (name "5V_DCDC") (class "Default")
      (node (ref "C2") (pin "2") (pinfunction "2_2") (pintype "passive"))
      (node (ref "C31") (pin "1") (pinfunction "1_1") (pintype "passive"))
      (node (ref "D15") (pin "A") (pinfunction "A_A") (pintype "passive"))
      (node (ref "E0") (pin "10") (pinfunction "VDD_10") (pintype "passive"))
      (node (ref "E0_MS") (pin "1") (pinfunction "A1_1") (pintype "passive"))
      (node (ref "E0_MS") (pin "2") (pinfunction "A2_2") (pintype "passive"))
      (node (ref "E0_MS") (pin "3") (pinfunction "A3_3") (pintype "passive"))
      (node (ref "E1") (pin "10") (pinfunction "VDD_10") (pintype "passive"))
      (node (ref "E1_MS") (pin "1") (pinfunction "A1_1") (pintype "passive"))
      (node (ref "E1_MS") (pin "2") (pinfunction "A2_2") (pintype "passive"))
      (node (ref "E1_MS") (pin "3") (pinfunction "A3_3") (pintype "passive"))
      (node (ref "E2") (pin "10") (pinfunction "VDD_10") (pintype "passive"))
      (node (ref "E2_MS") (pin "1") (pinfunction "A1_1") (pintype "passive"))
      (node (ref "E2_MS") (pin "2") (pinfunction "A2_2") (pintype "passive"))
      (node (ref "E2_MS") (pin "3") (pinfunction "A3_3") (pintype "passive"))
      (node (ref "L3") (pin "2") (pinfunction "2_2") (pintype "passive"))
      (node (ref "R20") (pin "2") (pinfunction "2_2") (pintype "passive"))
      (node (ref "R21") (pin "1") (pinfunction "1_1") (pintype "passive"))
      (node (ref "R23") (pin "1") (pinfunction "1_1") (pintype "passive"))
      (node (ref "R25") (pin "1") (pinfunction "1_1") (pintype "passive"))
      (node (ref "R27") (pin "1") (pinfunction "1_1") (pintype "passive"))
      (node (ref "R29") (pin "1") (pinfunction "1_1") (pintype "passive"))
      (node (ref "R45") (pin "1") (pinfunction "1_1") (pintype "passive"))
      (node (ref "R5") (pin "2") (pinfunction "2_2") (pintype "passive"))
      (node (ref "U4") (pin "8") (pinfunction "EN_8") (pintype "passive"))
      (node (ref "X") (pin "10") (pinfunction "VDD_10") (pintype "passive"))
      (node (ref "X_MS") (pin "1") (pinfunction "A1_1") (pintype "passive"))
      (node (ref "X_MS") (pin "2") (pinfunction "A2_2") (pintype "passive"))
      (node (ref "X_MS") (pin "3") (pinfunction "A3_3") (pintype "passive"))
      (node (ref "Y") (pin "10") (pinfunction "VDD_10") (pintype "passive"))
      (node (ref "Y_MS") (pin "1") (pinfunction "A1_1") (pintype "passive"))
      (node (ref "Y_MS") (pin "2") (pinfunction "A2_2") (pintype "passive"))
      (node (ref "Y_MS") (pin "3") (pinfunction "A3_3") (pintype "passive"))
      (node (ref "Z") (pin "10") (pinfunction "VDD_10") (pintype "passive"))
      (node (ref "Z_MS") (pin "1") (pinfunction "A1_1") (pintype "passive"))
      (node (ref "Z_MS") (pin "2") (pinfunction "A2_2") (pintype "passive"))
      (node (ref "Z_MS") (pin "3") (pinfunction "A3_3") (pintype "passive"))
    )
    (net (code "83") (name "GND") (class "Default")
      (node (ref "12V") (pin "2") (pinfunction "2_2") (pintype "passive"))
      (node (ref "5V") (pin "2") (pinfunction "2_2") (pintype "passive"))
      (node (ref "C1") (pin "2") (pinfunction "2_2") (pintype "passive"))
      (node (ref "C10") (pin "2") (pinfunction "2_2") (pintype "passive"))
      (node (ref "C11") (pin "1") (pinfunction "1_1") (pintype "passive"))
      (node (ref "C12") (pin "2") (pinfunction "2_2") (pintype "passive"))
      (node (ref "C13") (pin "1") (pinfunction "1_1") (pintype "passive"))
      (node (ref "C14") (pin "1") (pinfunction "1_1") (pintype "passive"))
      (node (ref "C15") (pin "1") (pinfunction "1_1") (pintype "passive"))
      (node (ref "C17") (pin "1") (pinfunction "1_1") (pintype "passive"))
      (node (ref "C19") (pin "1") (pinfunction "1_1") (pintype "passive"))
      (node (ref "C2") (pin "1") (pinfunction "1_1") (pintype "passive"))
      (node (ref "C20") (pin "1") (pinfunction "1_1") (pintype "passive"))
      (node (ref "C21") (pin "2") (pinfunction "2_2") (pintype "passive"))
      (node (ref "C22") (pin "2") (pinfunction "2_2") (pintype "passive"))
      (node (ref "C23") (pin "2") (pinfunction "2_2") (pintype "passive"))
      (node (ref "C24") (pin "2") (pinfunction "2_2") (pintype "passive"))
      (node (ref "C25") (pin "2") (pinfunction "2_2") (pintype "passive"))
      (node (ref "C26") (pin "2") (pinfunction "2_2") (pintype "passive"))
      (node (ref "C27") (pin "2") (pinfunction "2_2") (pintype "passive"))
      (node (ref "C28") (pin "2") (pinfunction "2_2") (pintype "passive"))
      (node (ref "C29") (pin "2") (pinfunction "2_2") (pintype "passive"))
      (node (ref "C3") (pin "1") (pinfunction "1_1") (pintype "passive"))
      (node (ref "C30") (pin "2") (pinfunction "2_2") (pintype "passive"))
      (node (ref "C31") (pin "2") (pinfunction "2_2") (pintype "passive"))
      (node (ref "C32") (pin "2") (pinfunction "2_2") (pintype "passive"))
      (node (ref "C34") (pin "1") (pinfunction "1_1") (pintype "passive"))
      (node (ref "C35") (pin "1") (pinfunction "1_1") (pintype "passive"))
      (node (ref "C36") (pin "1") (pinfunction "1_1") (pintype "passive"))
      (node (ref "C4") (pin "1") (pinfunction "1_1") (pintype "passive"))
      (node (ref "C5") (pin "1") (pinfunction "1_1") (pintype "passive"))
      (node (ref "C6") (pin "1") (pinfunction "1_1") (pintype "passive"))
      (node (ref "C7") (pin "1") (pinfunction "1_1") (pintype "passive"))
      (node (ref "C8") (pin "1") (pinfunction "1_1") (pintype "passive"))
      (node (ref "C9") (pin "2") (pinfunction "2_2") (pintype "passive"))
      (node (ref "D5") (pin "A") (pinfunction "A_A") (pintype "passive"))
      (node (ref "D6") (pin "A") (pinfunction "A_A") (pintype "passive"))
      (node (ref "D7") (pin "A") (pinfunction "A_A") (pintype "passive"))
      (node (ref "D8") (pin "A") (pinfunction "A_A") (pintype "passive"))
      (node (ref "E0") (pin "15") (pinfunction "GND_15") (pintype "passive"))
      (node (ref "E0") (pin "9") (pinfunction "GND_9") (pintype "passive"))
      (node (ref "E1") (pin "15") (pinfunction "GND_15") (pintype "passive"))
      (node (ref "E1") (pin "9") (pinfunction "GND_9") (pintype "passive"))
      (node (ref "E2") (pin "15") (pinfunction "GND_15") (pintype "passive"))
      (node (ref "E2") (pin "9") (pinfunction "GND_9") (pintype "passive"))
      (node (ref "ENC_1") (pin "3") (pinfunction "3_3") (pintype "passive"))
      (node (ref "ENC_2") (pin "3") (pinfunction "3_3") (pintype "passive"))
      (node (ref "ENC_3") (pin "3") (pinfunction "3_3") (pintype "passive"))
      (node (ref "ENC_4") (pin "3") (pinfunction "3_3") (pintype "passive"))
      (node (ref "EXP1") (pin "9") (pinfunction "9_9") (pintype "passive"))
      (node (ref "EXP2") (pin "9") (pinfunction "9_9") (pintype "passive"))
      (node (ref "EXP3") (pin "3") (pinfunction "3_3") (pintype "passive"))
      (node (ref "EXP3") (pin "4") (pinfunction "4_4") (pintype "passive"))
      (node (ref "HB-PWR") (pin "1") (pinfunction "4_1") (pintype "power_in"))
      (node (ref "ISP1") (pin "6") (pinfunction "6_6") (pintype "passive"))
      (node (ref "ISP2") (pin "6") (pinfunction "6_6") (pintype "passive"))
      (node (ref "J2") (pin "GND") (pinfunction "GND_GND") (pintype "passive"))
      (node (ref "JTAG") (pin "10") (pinfunction "10_10") (pintype "passive"))
      (node (ref "JTAG") (pin "2") (pinfunction "2_2") (pintype "passive"))
      (node (ref "L1") (pin "2") (pinfunction "2_2") (pintype "passive"))
      (node (ref "LD1") (pin "2") (pinfunction "K_2") (pintype "passive"))
      (node (ref "LD10") (pin "2") (pinfunction "K_2") (pintype "passive"))
      (node (ref "LD2") (pin "2") (pinfunction "K_2") (pintype "passive"))
      (node (ref "LD3") (pin "2") (pinfunction "K_2") (pintype "passive"))
      (node (ref "LD4") (pin "2") (pinfunction "K_2") (pintype "passive"))
      (node (ref "LD5") (pin "2") (pinfunction "K_2") (pintype "passive"))
      (node (ref "LD6") (pin "2") (pinfunction "K_2") (pintype "passive"))
      (node (ref "LD7") (pin "2") (pinfunction "K_2") (pintype "passive"))
      (node (ref "LD8") (pin "2") (pinfunction "K_2") (pintype "passive"))
      (node (ref "LD9") (pin "2") (pinfunction "K_2") (pintype "passive"))
      (node (ref "LED1") (pin "2") (pinfunction "K_2") (pintype "passive"))
      (node (ref "MAIN-PWR") (pin "1") (pinfunction "4_1") (pintype "power_in"))
      (node (ref "PS_ON") (pin "2") (pinfunction "2_2") (pintype "passive"))
      (node (ref "PWR") (pin "2") (pinfunction "2_2") (pintype "passive"))
      (node (ref "Q1") (pin "3") (pinfunction "S_3") (pintype "passive"))
      (node (ref "Q2") (pin "3") (pinfunction "S_3") (pintype "passive"))
      (node (ref "Q3") (pin "3") (pinfunction "S_3") (pintype "passive"))
      (node (ref "Q4") (pin "3") (pinfunction "S_3") (pintype "passive"))
      (node (ref "Q5") (pin "3") (pinfunction "S_3") (pintype "passive"))
      (node (ref "Q6") (pin "3") (pinfunction "S_3") (pintype "passive"))
      (node (ref "R10") (pin "1") (pinfunction "1_1") (pintype "passive"))
      (node (ref "R14") (pin "2") (pinfunction "2_2") (pintype "passive"))
      (node (ref "R22") (pin "2") (pinfunction "2_2") (pintype "passive"))
      (node (ref "R24") (pin "2") (pinfunction "2_2") (pintype "passive"))
      (node (ref "R26") (pin "2") (pinfunction "2_2") (pintype "passive"))
      (node (ref "R28") (pin "2") (pinfunction "2_2") (pintype "passive"))
      (node (ref "R30") (pin "2") (pinfunction "2_2") (pintype "passive"))
      (node (ref "R32") (pin "2") (pinfunction "2_2") (pintype "passive"))
      (node (ref "R35") (pin "2") (pinfunction "2_2") (pintype "passive"))
      (node (ref "R38") (pin "2") (pinfunction "2_2") (pintype "passive"))
      (node (ref "R44") (pin "2") (pinfunction "2_2") (pintype "passive"))
      (node (ref "R47") (pin "2") (pinfunction "2_2") (pintype "passive"))
      (node (ref "R49") (pin "2") (pinfunction "2_2") (pintype "passive"))
      (node (ref "R52") (pin "2") (pinfunction "2_2") (pintype "passive"))
      (node (ref "R57") (pin "1") (pinfunction "1_1") (pintype "passive"))
      (node (ref "R6") (pin "1") (pinfunction "1_1") (pintype "passive"))
      (node (ref "Reset") (pin "1") (pintype "passive"))
      (node (ref "Thermistors") (pin "1") (pinfunction "1_1") (pintype "passive"))
      (node (ref "Thermistors") (pin "3") (pinfunction "3_3") (pintype "passive"))
      (node (ref "Thermistors") (pin "5") (pinfunction "5_5") (pintype "passive"))
      (node (ref "Thermistors") (pin "7") (pinfunction "7_7") (pintype "passive"))
      (node (ref "Thermistors") (pin "9") (pinfunction "9_9") (pintype "passive"))
      (node (ref "U1") (pin "11") (pinfunction "GND_11") (pintype "passive"))
      (node (ref "U1") (pin "32") (pinfunction "GND_32") (pintype "passive"))
      (node (ref "U1") (pin "62") (pinfunction "GND_62") (pintype "passive"))
      (node (ref "U1") (pin "81") (pinfunction "GND_81") (pintype "passive"))
      (node (ref "U1") (pin "99") (pinfunction "AGND_99") (pintype "passive"))
      (node (ref "U2") (pin "28") (pinfunction "UGND_28") (pintype "passive"))
      (node (ref "U2") (pin "3") (pinfunction "GND_3") (pintype "passive"))
      (node (ref "U2") (pin "33") (pinfunction "PAD_33") (pintype "passive"))
      (node (ref "U3") (pin "2") (pinfunction "GND_2") (pintype "passive"))
      (node (ref "U4") (pin "3") (pinfunction "GND_3") (pintype "passive"))
      (node (ref "U5") (pin "2") (pinfunction "GND_2") (pintype "passive"))
      (node (ref "USB_AUX") (pin "2") (pinfunction "2_2") (pintype "passive"))
      (node (ref "X") (pin "15") (pinfunction "GND_15") (pintype "passive"))
      (node (ref "X") (pin "9") (pinfunction "GND_9") (pintype "passive"))
      (node (ref "X+") (pin "2") (pinfunction "2_2") (pintype "passive"))
      (node (ref "X-") (pin "2") (pinfunction "2_2") (pintype "passive"))
      (node (ref "Y") (pin "15") (pinfunction "GND_15") (pintype "passive"))
      (node (ref "Y") (pin "9") (pinfunction "GND_9") (pintype "passive"))
      (node (ref "Y+") (pin "2") (pinfunction "2_2") (pintype "passive"))
      (node (ref "Y-") (pin "2") (pinfunction "2_2") (pintype "passive"))
      (node (ref "Z") (pin "15") (pinfunction "GND_15") (pintype "passive"))
      (node (ref "Z") (pin "9") (pinfunction "GND_9") (pintype "passive"))
      (node (ref "Z+") (pin "2") (pinfunction "2_2") (pintype "passive"))
      (node (ref "Z-") (pin "2") (pinfunction "2_2") (pintype "passive"))
    )
    (net (code "84") (name "Net-(C10-Pad1)") (class "Default")
      (node (ref "C10") (pin "1") (pinfunction "1_1") (pintype "passive"))
      (node (ref "R19") (pin "1") (pinfunction "1_1") (pintype "passive"))
    )
    (net (code "85") (name "Net-(D4-PadA)") (class "Default")
      (node (ref "D4") (pin "A") (pinfunction "A_A") (pintype "passive"))
      (node (ref "F3") (pin "2") (pinfunction "2_2") (pintype "passive"))
    )
    (net (code "86") (name "Net-(E0-1A)") (class "Default")
      (node (ref "E0") (pin "12") (pinfunction "1A_12") (pintype "passive"))
      (node (ref "E0_MOT") (pin "2") (pinfunction "2_2") (pintype "passive"))
      (node (ref "E0_MOT_A") (pin "3") (pinfunction "3_3") (pintype "passive"))
    )
    (net (code "87") (name "Net-(E0-1B)") (class "Default")
      (node (ref "E0") (pin "11") (pinfunction "1B_11") (pintype "passive"))
      (node (ref "E0_MOT") (pin "1") (pinfunction "1_1") (pintype "passive"))
      (node (ref "E0_MOT_A") (pin "4") (pinfunction "4_4") (pintype "passive"))
    )
    (net (code "88") (name "Net-(E0-2A)") (class "Default")
      (node (ref "E0") (pin "13") (pinfunction "2A_13") (pintype "passive"))
      (node (ref "E0_MOT") (pin "3") (pinfunction "3_3") (pintype "passive"))
      (node (ref "E0_MOT_A") (pin "2") (pinfunction "2_2") (pintype "passive"))
    )
    (net (code "89") (name "Net-(E0-2B)") (class "Default")
      (node (ref "E0") (pin "14") (pinfunction "2B_14") (pintype "passive"))
      (node (ref "E0_MOT") (pin "4") (pinfunction "4_4") (pintype "passive"))
      (node (ref "E0_MOT_A") (pin "1") (pinfunction "1_1") (pintype "passive"))
    )
    (net (code "90") (name "Net-(E0-MS1)") (class "Default")
      (node (ref "E0") (pin "2") (pinfunction "MS1_2") (pintype "passive"))
      (node (ref "E0_MS") (pin "4") (pinfunction "B3_4") (pintype "passive"))
      (node (ref "R28") (pin "1") (pinfunction "1_1") (pintype "passive"))
    )
    (net (code "91") (name "Net-(E0-MS2)") (class "Default")
      (node (ref "E0") (pin "3") (pinfunction "MS2_3") (pintype "passive"))
      (node (ref "E0_MS") (pin "5") (pinfunction "B2_5") (pintype "passive"))
    )
    (net (code "92") (name "Net-(E0-MS3)") (class "Default")
      (node (ref "E0") (pin "4") (pinfunction "MS3_4") (pintype "passive"))
      (node (ref "E0_MS") (pin "6") (pinfunction "B1_6") (pintype "passive"))
    )
    (net (code "93") (name "Net-(E0-~{RST})") (class "Default")
      (node (ref "E0") (pin "5") (pinfunction "~{RST}_5") (pintype "passive"))
      (node (ref "E0") (pin "6") (pinfunction "~{SLEEP}_6") (pintype "passive"))
    )
    (net (code "94") (name "Net-(E1-1A)") (class "Default")
      (node (ref "E1") (pin "12") (pinfunction "1A_12") (pintype "passive"))
      (node (ref "E1_MOT") (pin "2") (pinfunction "2_2") (pintype "passive"))
      (node (ref "E1_MOT_A") (pin "3") (pinfunction "3_3") (pintype "passive"))
    )
    (net (code "95") (name "Net-(E1-1B)") (class "Default")
      (node (ref "E1") (pin "11") (pinfunction "1B_11") (pintype "passive"))
      (node (ref "E1_MOT") (pin "1") (pinfunction "1_1") (pintype "passive"))
      (node (ref "E1_MOT_A") (pin "4") (pinfunction "4_4") (pintype "passive"))
    )
    (net (code "96") (name "Net-(E1-2A)") (class "Default")
      (node (ref "E1") (pin "13") (pinfunction "2A_13") (pintype "passive"))
      (node (ref "E1_MOT") (pin "3") (pinfunction "3_3") (pintype "passive"))
      (node (ref "E1_MOT_A") (pin "2") (pinfunction "2_2") (pintype "passive"))
    )
    (net (code "97") (name "Net-(E1-2B)") (class "Default")
      (node (ref "E1") (pin "14") (pinfunction "2B_14") (pintype "passive"))
      (node (ref "E1_MOT") (pin "4") (pinfunction "4_4") (pintype "passive"))
      (node (ref "E1_MOT_A") (pin "1") (pinfunction "1_1") (pintype "passive"))
    )
    (net (code "98") (name "Net-(E1-MS1)") (class "Default")
      (node (ref "E1") (pin "2") (pinfunction "MS1_2") (pintype "passive"))
      (node (ref "E1_MS") (pin "4") (pinfunction "B3_4") (pintype "passive"))
      (node (ref "R30") (pin "1") (pinfunction "1_1") (pintype "passive"))
    )
    (net (code "99") (name "Net-(E1-MS2)") (class "Default")
      (node (ref "E1") (pin "3") (pinfunction "MS2_3") (pintype "passive"))
      (node (ref "E1_MS") (pin "5") (pinfunction "B2_5") (pintype "passive"))
    )
    (net (code "100") (name "Net-(E1-MS3)") (class "Default")
      (node (ref "E1") (pin "4") (pinfunction "MS3_4") (pintype "passive"))
      (node (ref "E1_MS") (pin "6") (pinfunction "B1_6") (pintype "passive"))
    )
    (net (code "101") (name "Net-(E1-~{RST})") (class "Default")
      (node (ref "E1") (pin "5") (pinfunction "~{RST}_5") (pintype "passive"))
      (node (ref "E1") (pin "6") (pinfunction "~{SLEEP}_6") (pintype "passive"))
    )
    (net (code "102") (name "Net-(E2-1A)") (class "Default")
      (node (ref "E2") (pin "12") (pinfunction "1A_12") (pintype "passive"))
      (node (ref "E2_MOT") (pin "2") (pinfunction "2_2") (pintype "passive"))
      (node (ref "E2_MOT_A") (pin "3") (pinfunction "3_3") (pintype "passive"))
    )
    (net (code "103") (name "Net-(E2-1B)") (class "Default")
      (node (ref "E2") (pin "11") (pinfunction "1B_11") (pintype "passive"))
      (node (ref "E2_MOT") (pin "1") (pinfunction "1_1") (pintype "passive"))
      (node (ref "E2_MOT_A") (pin "4") (pinfunction "4_4") (pintype "passive"))
    )
    (net (code "104") (name "Net-(E2-2A)") (class "Default")
      (node (ref "E2") (pin "13") (pinfunction "2A_13") (pintype "passive"))
      (node (ref "E2_MOT") (pin "3") (pinfunction "3_3") (pintype "passive"))
      (node (ref "E2_MOT_A") (pin "2") (pinfunction "2_2") (pintype "passive"))
    )
    (net (code "105") (name "Net-(E2-2B)") (class "Default")
      (node (ref "E2") (pin "14") (pinfunction "2B_14") (pintype "passive"))
      (node (ref "E2_MOT") (pin "4") (pinfunction "4_4") (pintype "passive"))
      (node (ref "E2_MOT_A") (pin "1") (pinfunction "1_1") (pintype "passive"))
    )
    (net (code "106") (name "Net-(E2-MS1)") (class "Default")
      (node (ref "E2") (pin "2") (pinfunction "MS1_2") (pintype "passive"))
      (node (ref "E2_MS") (pin "4") (pinfunction "B3_4") (pintype "passive"))
      (node (ref "R44") (pin "1") (pinfunction "1_1") (pintype "passive"))
    )
    (net (code "107") (name "Net-(E2-MS2)") (class "Default")
      (node (ref "E2") (pin "3") (pinfunction "MS2_3") (pintype "passive"))
      (node (ref "E2_MS") (pin "5") (pinfunction "B2_5") (pintype "passive"))
    )
    (net (code "108") (name "Net-(E2-MS3)") (class "Default")
      (node (ref "E2") (pin "4") (pinfunction "MS3_4") (pintype "passive"))
      (node (ref "E2_MS") (pin "6") (pinfunction "B1_6") (pintype "passive"))
    )
    (net (code "109") (name "Net-(E2-~{RST})") (class "Default")
      (node (ref "E2") (pin "5") (pinfunction "~{RST}_5") (pintype "passive"))
      (node (ref "E2") (pin "6") (pinfunction "~{SLEEP}_6") (pintype "passive"))
    )
    (net (code "110") (name "Net-(F1-Pad0)") (class "Default")
      (node (ref "F1") (pin "0") (pinfunction "0_0") (pintype "passive"))
      (node (ref "HB-PWR") (pin "2") (pinfunction "2_2") (pintype "power_in"))
    )
    (net (code "111") (name "Net-(F2-Pad0)") (class "Default")
      (node (ref "F2") (pin "0") (pinfunction "0_0") (pintype "passive"))
      (node (ref "MAIN-PWR") (pin "2") (pinfunction "2_2") (pintype "power_in"))
    )
    (net (code "112") (name "Net-(FAN0-4)") (class "Default")
      (node (ref "D10") (pin "K") (pinfunction "K_K") (pintype "passive"))
      (node (ref "FAN0") (pin "1") (pinfunction "4_1") (pintype "power_in"))
      (node (ref "FAN0_1") (pin "1") (pinfunction "1_1") (pintype "passive"))
      (node (ref "VFA0_sel") (pin "2") (pinfunction "2_2") (pintype "passive"))
    )
    (net (code "113") (name "Net-(FAN1-4)") (class "Default")
      (node (ref "D11") (pin "K") (pinfunction "K_K") (pintype "passive"))
      (node (ref "FAN1") (pin "1") (pinfunction "4_1") (pintype "power_in"))
      (node (ref "FAN1_1") (pin "1") (pinfunction "1_1") (pintype "passive"))
      (node (ref "VFA1_sel") (pin "2") (pinfunction "2_2") (pintype "passive"))
    )
    (net (code "114") (name "Net-(HB-OUT-4)") (class "Default")
      (node (ref "D13") (pin "A") (pinfunction "A_A") (pintype "passive"))
      (node (ref "HB-OUT") (pin "1") (pinfunction "4_1") (pintype "power_in"))
      (node (ref "Q6") (pin "2") (pinfunction "D_2") (pintype "passive"))
    )
    (net (code "115") (name "Net-(HE2-4)") (class "Default")
      (node (ref "D14") (pin "K") (pinfunction "K_K") (pintype "passive"))
      (node (ref "HE2") (pin "1") (pinfunction "4_1") (pintype "power_in"))
      (node (ref "VHE2_sel") (pin "2") (pinfunction "2_2") (pintype "passive"))
    )
    (net (code "116") (name "Net-(J2-SH)") (class "Default")
      (node (ref "J2") (pin "SHIELD") (pinfunction "SH_SHIELD") (pintype "passive"))
      (node (ref "L1") (pin "1") (pinfunction "1_1") (pintype "passive"))
      (node (ref "USB_AUX") (pin "1") (pinfunction "1_1") (pintype "passive"))
    )
    (net (code "117") (name "Net-(LD1-A)") (class "Default")
      (node (ref "LD1") (pin "1") (pinfunction "A_1") (pintype "passive"))
      (node (ref "R4") (pin "1") (pinfunction "1_1") (pintype "passive"))
    )
    (net (code "118") (name "Net-(LD2-A)") (class "Default")
      (node (ref "LD2") (pin "1") (pinfunction "A_1") (pintype "passive"))
      (node (ref "R33") (pin "1") (pinfunction "1_1") (pintype "passive"))
    )
    (net (code "119") (name "Net-(LD3-A)") (class "Default")
      (node (ref "LD3") (pin "1") (pinfunction "A_1") (pintype "passive"))
      (node (ref "R36") (pin "1") (pinfunction "1_1") (pintype "passive"))
    )
    (net (code "120") (name "Net-(LD4-A)") (class "Default")
      (node (ref "LD4") (pin "1") (pinfunction "A_1") (pintype "passive"))
      (node (ref "R39") (pin "1") (pinfunction "1_1") (pintype "passive"))
    )
    (net (code "121") (name "Net-(LD5-A)") (class "Default")
      (node (ref "LD5") (pin "1") (pinfunction "A_1") (pintype "passive"))
      (node (ref "R50") (pin "1") (pinfunction "1_1") (pintype "passive"))
    )
    (net (code "122") (name "Net-(LD6-A)") (class "Default")
      (node (ref "LD6") (pin "1") (pinfunction "A_1") (pintype "passive"))
      (node (ref "R53") (pin "1") (pinfunction "1_1") (pintype "passive"))
    )
    (net (code "123") (name "Net-(LD7-A)") (class "Default")
      (node (ref "LD7") (pin "1") (pinfunction "A_1") (pintype "passive"))
      (node (ref "R55") (pin "1") (pinfunction "1_1") (pintype "passive"))
    )
    (net (code "124") (name "Net-(LD8-A)") (class "Default")
      (node (ref "LD8") (pin "1") (pinfunction "A_1") (pintype "passive"))
      (node (ref "R20") (pin "1") (pinfunction "1_1") (pintype "passive"))
    )
    (net (code "125") (name "Net-(LD9-A)") (class "Default")
      (node (ref "LD9") (pin "1") (pinfunction "A_1") (pintype "passive"))
      (node (ref "R58") (pin "1") (pinfunction "1_1") (pintype "passive"))
    )
    (net (code "126") (name "Net-(LD10-A)") (class "Default")
      (node (ref "LD10") (pin "1") (pinfunction "A_1") (pintype "passive"))
      (node (ref "R59") (pin "1") (pinfunction "1_1") (pintype "passive"))
    )
    (net (code "127") (name "Net-(LED1-A)") (class "Default")
      (node (ref "LED1") (pin "1") (pinfunction "A_1") (pintype "passive"))
      (node (ref "R13") (pin "1") (pinfunction "1_1") (pintype "passive"))
    )
    (net (code "128") (name "Net-(Q1-D)") (class "Default")
      (node (ref "D12") (pin "A") (pinfunction "A_A") (pintype "passive"))
      (node (ref "HE0") (pin "2") (pinfunction "2_2") (pintype "power_in"))
      (node (ref "Q1") (pin "2") (pinfunction "D_2") (pintype "passive"))
    )
    (net (code "129") (name "Net-(Q1-G)") (class "Default")
      (node (ref "Q1") (pin "1") (pinfunction "G_1") (pintype "passive"))
      (node (ref "R34") (pin "2") (pinfunction "2_2") (pintype "passive"))
    )
    (net (code "130") (name "Net-(Q2-D)") (class "Default")
      (node (ref "D9") (pin "A") (pinfunction "A_A") (pintype "passive"))
      (node (ref "HE1") (pin "2") (pinfunction "2_2") (pintype "power_in"))
      (node (ref "Q2") (pin "2") (pinfunction "D_2") (pintype "passive"))
    )
    (net (code "131") (name "Net-(Q2-G)") (class "Default")
      (node (ref "Q2") (pin "1") (pinfunction "G_1") (pintype "passive"))
      (node (ref "R37") (pin "2") (pinfunction "2_2") (pintype "passive"))
    )
    (net (code "132") (name "Net-(Q3-D)") (class "Default")
      (node (ref "D14") (pin "A") (pinfunction "A_A") (pintype "passive"))
      (node (ref "HE2") (pin "2") (pinfunction "2_2") (pintype "power_in"))
      (node (ref "Q3") (pin "2") (pinfunction "D_2") (pintype "passive"))
    )
    (net (code "133") (name "Net-(Q3-G)") (class "Default")
      (node (ref "Q3") (pin "1") (pinfunction "G_1") (pintype "passive"))
      (node (ref "R48") (pin "2") (pinfunction "2_2") (pintype "passive"))
    )
    (net (code "134") (name "Net-(Q4-D)") (class "Default")
      (node (ref "D10") (pin "A") (pinfunction "A_A") (pintype "passive"))
      (node (ref "FAN0") (pin "2") (pinfunction "2_2") (pintype "power_in"))
      (node (ref "FAN0_1") (pin "2") (pinfunction "2_2") (pintype "passive"))
      (node (ref "Q4") (pin "2") (pinfunction "D_2") (pintype "passive"))
    )
    (net (code "135") (name "Net-(Q4-G)") (class "Default")
      (node (ref "Q4") (pin "1") (pinfunction "G_1") (pintype "passive"))
      (node (ref "R51") (pin "2") (pinfunction "2_2") (pintype "passive"))
    )
    (net (code "136") (name "Net-(Q5-D)") (class "Default")
      (node (ref "D11") (pin "A") (pinfunction "A_A") (pintype "passive"))
      (node (ref "FAN1") (pin "2") (pinfunction "2_2") (pintype "power_in"))
      (node (ref "FAN1_1") (pin "2") (pinfunction "2_2") (pintype "passive"))
      (node (ref "Q5") (pin "2") (pinfunction "D_2") (pintype "passive"))
    )
    (net (code "137") (name "Net-(Q5-G)") (class "Default")
      (node (ref "Q5") (pin "1") (pinfunction "G_1") (pintype "passive"))
      (node (ref "R46") (pin "2") (pinfunction "2_2") (pintype "passive"))
    )
    (net (code "138") (name "Net-(Q6-G)") (class "Default")
      (node (ref "Q6") (pin "1") (pinfunction "G_1") (pintype "passive"))
      (node (ref "R31") (pin "2") (pinfunction "2_2") (pintype "passive"))
    )
    (net (code "139") (name "Net-(RX-A)") (class "Default")
      (node (ref "R16") (pin "2") (pinfunction "2_2") (pintype "passive"))
      (node (ref "RX") (pin "1") (pinfunction "A_1") (pintype "passive"))
    )
    (net (code "140") (name "Net-(RX-K)") (class "Default")
      (node (ref "RX") (pin "2") (pinfunction "K_2") (pintype "passive"))
      (node (ref "U2") (pin "10") (pinfunction "(INT5/AIN3)PD4_10") (pintype "passive"))
    )
    (net (code "141") (name "Net-(TX-A)") (class "Default")
      (node (ref "R15") (pin "2") (pinfunction "2_2") (pintype "passive"))
      (node (ref "TX") (pin "1") (pinfunction "A_1") (pintype "passive"))
    )
    (net (code "142") (name "Net-(TX-K)") (class "Default")
      (node (ref "TX") (pin "2") (pinfunction "K_2") (pintype "passive"))
      (node (ref "U2") (pin "11") (pinfunction "(XCK/AIN4/PCINT12)PD5_11") (pintype "passive"))
    )
    (net (code "143") (name "Net-(U1-XTAL1)") (class "Default")
      (node (ref "C20") (pin "2") (pinfunction "2_2") (pintype "passive"))
      (node (ref "R1") (pin "1") (pinfunction "1_1") (pintype "passive"))
      (node (ref "U1") (pin "34") (pinfunction "XTAL1_34") (pintype "passive"))
      (node (ref "Y1") (pin "1") (pinfunction "OSC1_1") (pintype "passive"))
    )
    (net (code "144") (name "Net-(U1-XTAL2)") (class "Default")
      (node (ref "C19") (pin "2") (pinfunction "2_2") (pintype "passive"))
      (node (ref "R1") (pin "2") (pinfunction "2_2") (pintype "passive"))
      (node (ref "U1") (pin "33") (pinfunction "XTAL2_33") (pintype "passive"))
      (node (ref "Y1") (pin "3") (pinfunction "OSC2_3") (pintype "passive"))
    )
    (net (code "145") (name "Net-(U2-(RXD1{slash}AIN1{slash}INT2)PD2)") (class "Default")
      (node (ref "R17") (pin "1") (pinfunction "1_1") (pintype "passive"))
      (node (ref "U2") (pin "8") (pinfunction "(RXD1/AIN1/INT2)PD2_8") (pintype "passive"))
    )
    (net (code "146") (name "Net-(U2-(TXD1{slash}INT3)PD3)") (class "Default")
      (node (ref "R18") (pin "1") (pinfunction "1_1") (pintype "passive"))
      (node (ref "U2") (pin "9") (pinfunction "(TXD1/INT3)PD3_9") (pintype "passive"))
    )
    (net (code "147") (name "Net-(U2-D+)") (class "Default")
      (node (ref "R8") (pin "1") (pinfunction "1_1") (pintype "passive"))
      (node (ref "U2") (pin "29") (pinfunction "D+_29") (pintype "passive"))
    )
    (net (code "148") (name "Net-(U2-D-)") (class "Default")
      (node (ref "R7") (pin "1") (pinfunction "1_1") (pintype "passive"))
      (node (ref "U2") (pin "30") (pinfunction "D-_30") (pintype "passive"))
    )
    (net (code "149") (name "Net-(U2-UCAP)") (class "Default")
      (node (ref "C12") (pin "1") (pinfunction "1_1") (pintype "passive"))
      (node (ref "U2") (pin "27") (pinfunction "UCAP_27") (pintype "passive"))
    )
    (net (code "150") (name "Net-(U2-XTAL1)") (class "Default")
      (node (ref "C14") (pin "2") (pinfunction "2_2") (pintype "passive"))
      (node (ref "R9") (pin "1") (pinfunction "1_1") (pintype "passive"))
      (node (ref "U2") (pin "1") (pinfunction "XTAL1_1") (pintype "passive"))
      (node (ref "Y2") (pin "1") (pinfunction "OSC1_1") (pintype "passive"))
    )
    (net (code "151") (name "Net-(U2-XTAL2(PC0))") (class "Default")
      (node (ref "C15") (pin "2") (pinfunction "2_2") (pintype "passive"))
      (node (ref "R9") (pin "2") (pinfunction "2_2") (pintype "passive"))
      (node (ref "U2") (pin "2") (pinfunction "XTAL2(PC0)_2") (pintype "passive"))
      (node (ref "Y2") (pin "3") (pinfunction "OSC2_3") (pintype "passive"))
    )
    (net (code "152") (name "Net-(U3-BST)") (class "Default")
      (node (ref "C18") (pin "2") (pinfunction "2_2") (pintype "passive"))
      (node (ref "U3") (pin "1") (pinfunction "BST_1") (pintype "passive"))
    )
    (net (code "153") (name "Net-(U3-SW)") (class "Default")
      (node (ref "C18") (pin "1") (pinfunction "1_1") (pintype "passive"))
      (node (ref "D5") (pin "K") (pinfunction "K_K") (pintype "passive"))
      (node (ref "L3") (pin "1") (pinfunction "1_1") (pintype "passive"))
      (node (ref "U3") (pin "6") (pinfunction "SW_6") (pintype "passive"))
    )
    (net (code "154") (name "Net-(U4-BST)") (class "Default")
      (node (ref "C33") (pin "1") (pinfunction "1_1") (pintype "passive"))
      (node (ref "U4") (pin "2") (pinfunction "BST_2") (pintype "passive"))
    )
    (net (code "155") (name "Net-(U4-COMP)") (class "Default")
      (node (ref "R19") (pin "2") (pinfunction "2_2") (pintype "passive"))
      (node (ref "U4") (pin "5") (pinfunction "COMP_5") (pintype "passive"))
    )
    (net (code "156") (name "Net-(U4-FSW)") (class "Default")
      (node (ref "R10") (pin "2") (pinfunction "2_2") (pintype "passive"))
      (node (ref "U4") (pin "4") (pinfunction "FSW_4") (pintype "passive"))
    )
    (net (code "157") (name "Net-(U4-LX)") (class "Default")
      (node (ref "C33") (pin "2") (pinfunction "2_2") (pintype "passive"))
      (node (ref "D8") (pin "K") (pinfunction "K_K") (pintype "passive"))
      (node (ref "L4") (pin "1") (pinfunction "1_1") (pintype "passive"))
      (node (ref "U4") (pin "1") (pinfunction "LX_1") (pintype "passive"))
    )
    (net (code "158") (name "Net-(U4-SS)") (class "Default")
      (node (ref "C34") (pin "2") (pinfunction "2_2") (pintype "passive"))
      (node (ref "U4") (pin "7") (pinfunction "SS_7") (pintype "passive"))
    )
    (net (code "159") (name "Net-(U5-IO1)") (class "Default")
      (node (ref "J2") (pin "D-") (pinfunction "D-_D-") (pintype "passive"))
      (node (ref "R7") (pin "2") (pinfunction "2_2") (pintype "passive"))
      (node (ref "U5") (pin "1") (pinfunction "IO1_1") (pintype "passive"))
      (node (ref "USB_AUX") (pin "4") (pinfunction "4_4") (pintype "passive"))
    )
    (net (code "160") (name "Net-(U5-IO2)") (class "Default")
      (node (ref "J2") (pin "D+") (pinfunction "D+_D+") (pintype "passive"))
      (node (ref "R8") (pin "2") (pinfunction "2_2") (pintype "passive"))
      (node (ref "U5") (pin "3") (pinfunction "IO2_3") (pintype "passive"))
      (node (ref "USB_AUX") (pin "3") (pinfunction "3_3") (pintype "passive"))
    )
    (net (code "161") (name "Net-(X-1A)") (class "Default")
      (node (ref "X") (pin "12") (pinfunction "1A_12") (pintype "passive"))
      (node (ref "X_MOT") (pin "2") (pinfunction "2_2") (pintype "passive"))
      (node (ref "X_MOT_A") (pin "3") (pinfunction "3_3") (pintype "passive"))
    )
    (net (code "162") (name "Net-(X-1B)") (class "Default")
      (node (ref "X") (pin "11") (pinfunction "1B_11") (pintype "passive"))
      (node (ref "X_MOT") (pin "1") (pinfunction "1_1") (pintype "passive"))
      (node (ref "X_MOT_A") (pin "4") (pinfunction "4_4") (pintype "passive"))
    )
    (net (code "163") (name "Net-(X-2A)") (class "Default")
      (node (ref "X") (pin "13") (pinfunction "2A_13") (pintype "passive"))
      (node (ref "X_MOT") (pin "3") (pinfunction "3_3") (pintype "passive"))
      (node (ref "X_MOT_A") (pin "2") (pinfunction "2_2") (pintype "passive"))
    )
    (net (code "164") (name "Net-(X-2B)") (class "Default")
      (node (ref "X") (pin "14") (pinfunction "2B_14") (pintype "passive"))
      (node (ref "X_MOT") (pin "4") (pinfunction "4_4") (pintype "passive"))
      (node (ref "X_MOT_A") (pin "1") (pinfunction "1_1") (pintype "passive"))
    )
    (net (code "165") (name "Net-(X-MS1)") (class "Default")
      (node (ref "R22") (pin "1") (pinfunction "1_1") (pintype "passive"))
      (node (ref "X") (pin "2") (pinfunction "MS1_2") (pintype "passive"))
      (node (ref "X_MS") (pin "4") (pinfunction "B3_4") (pintype "passive"))
    )
    (net (code "166") (name "Net-(X-MS2)") (class "Default")
      (node (ref "X") (pin "3") (pinfunction "MS2_3") (pintype "passive"))
      (node (ref "X_MS") (pin "5") (pinfunction "B2_5") (pintype "passive"))
    )
    (net (code "167") (name "Net-(X-MS3)") (class "Default")
      (node (ref "X") (pin "4") (pinfunction "MS3_4") (pintype "passive"))
      (node (ref "X_MS") (pin "6") (pinfunction "B1_6") (pintype "passive"))
    )
    (net (code "168") (name "Net-(X-~{RST})") (class "Default")
      (node (ref "X") (pin "5") (pinfunction "~{RST}_5") (pintype "passive"))
      (node (ref "X") (pin "6") (pinfunction "~{SLEEP}_6") (pintype "passive"))
    )
    (net (code "169") (name "Net-(Y-1A)") (class "Default")
      (node (ref "Y") (pin "12") (pinfunction "1A_12") (pintype "passive"))
      (node (ref "Y_MOT") (pin "2") (pinfunction "2_2") (pintype "passive"))
      (node (ref "Y_MOT_A") (pin "3") (pinfunction "3_3") (pintype "passive"))
    )
    (net (code "170") (name "Net-(Y-1B)") (class "Default")
      (node (ref "Y") (pin "11") (pinfunction "1B_11") (pintype "passive"))
      (node (ref "Y_MOT") (pin "1") (pinfunction "1_1") (pintype "passive"))
      (node (ref "Y_MOT_A") (pin "4") (pinfunction "4_4") (pintype "passive"))
    )
    (net (code "171") (name "Net-(Y-2A)") (class "Default")
      (node (ref "Y") (pin "13") (pinfunction "2A_13") (pintype "passive"))
      (node (ref "Y_MOT") (pin "3") (pinfunction "3_3") (pintype "passive"))
      (node (ref "Y_MOT_A") (pin "2") (pinfunction "2_2") (pintype "passive"))
    )
    (net (code "172") (name "Net-(Y-2B)") (class "Default")
      (node (ref "Y") (pin "14") (pinfunction "2B_14") (pintype "passive"))
      (node (ref "Y_MOT") (pin "4") (pinfunction "4_4") (pintype "passive"))
      (node (ref "Y_MOT_A") (pin "1") (pinfunction "1_1") (pintype "passive"))
    )
    (net (code "173") (name "Net-(Y-MS1)") (class "Default")
      (node (ref "R24") (pin "1") (pinfunction "1_1") (pintype "passive"))
      (node (ref "Y") (pin "2") (pinfunction "MS1_2") (pintype "passive"))
      (node (ref "Y_MS") (pin "4") (pinfunction "B3_4") (pintype "passive"))
    )
    (net (code "174") (name "Net-(Y-MS2)") (class "Default")
      (node (ref "Y") (pin "3") (pinfunction "MS2_3") (pintype "passive"))
      (node (ref "Y_MS") (pin "5") (pinfunction "B2_5") (pintype "passive"))
    )
    (net (code "175") (name "Net-(Y-MS3)") (class "Default")
      (node (ref "Y") (pin "4") (pinfunction "MS3_4") (pintype "passive"))
      (node (ref "Y_MS") (pin "6") (pinfunction "B1_6") (pintype "passive"))
    )
    (net (code "176") (name "Net-(Y-~{RST})") (class "Default")
      (node (ref "Y") (pin "5") (pinfunction "~{RST}_5") (pintype "passive"))
      (node (ref "Y") (pin "6") (pinfunction "~{SLEEP}_6") (pintype "passive"))
    )
    (net (code "177") (name "Net-(Z-1A)") (class "Default")
      (node (ref "Z") (pin "12") (pinfunction "1A_12") (pintype "passive"))
      (node (ref "Z_MOT") (pin "2") (pinfunction "2_2") (pintype "passive"))
      (node (ref "Z_MOT_A") (pin "3") (pinfunction "3_3") (pintype "passive"))
    )
    (net (code "178") (name "Net-(Z-1B)") (class "Default")
      (node (ref "Z") (pin "11") (pinfunction "1B_11") (pintype "passive"))
      (node (ref "Z_MOT") (pin "1") (pinfunction "1_1") (pintype "passive"))
      (node (ref "Z_MOT_A") (pin "4") (pinfunction "4_4") (pintype "passive"))
    )
    (net (code "179") (name "Net-(Z-2A)") (class "Default")
      (node (ref "Z") (pin "13") (pinfunction "2A_13") (pintype "passive"))
      (node (ref "Z_MOT") (pin "3") (pinfunction "3_3") (pintype "passive"))
      (node (ref "Z_MOT_A") (pin "2") (pinfunction "2_2") (pintype "passive"))
    )
    (net (code "180") (name "Net-(Z-2B)") (class "Default")
      (node (ref "Z") (pin "14") (pinfunction "2B_14") (pintype "passive"))
      (node (ref "Z_MOT") (pin "4") (pinfunction "4_4") (pintype "passive"))
      (node (ref "Z_MOT_A") (pin "1") (pinfunction "1_1") (pintype "passive"))
    )
    (net (code "181") (name "Net-(Z-MS1)") (class "Default")
      (node (ref "R26") (pin "1") (pinfunction "1_1") (pintype "passive"))
      (node (ref "Z") (pin "2") (pinfunction "MS1_2") (pintype "passive"))
      (node (ref "Z_MS") (pin "4") (pinfunction "B3_4") (pintype "passive"))
    )
    (net (code "182") (name "Net-(Z-MS2)") (class "Default")
      (node (ref "Z") (pin "3") (pinfunction "MS2_3") (pintype "passive"))
      (node (ref "Z_MS") (pin "5") (pinfunction "B2_5") (pintype "passive"))
    )
    (net (code "183") (name "Net-(Z-MS3)") (class "Default")
      (node (ref "Z") (pin "4") (pinfunction "MS3_4") (pintype "passive"))
      (node (ref "Z_MS") (pin "6") (pinfunction "B1_6") (pintype "passive"))
    )
    (net (code "184") (name "Net-(Z-~{RST})") (class "Default")
      (node (ref "Z") (pin "5") (pinfunction "~{RST}_5") (pintype "passive"))
      (node (ref "Z") (pin "6") (pinfunction "~{SLEEP}_6") (pintype "passive"))
    )
    (net (code "185") (name "USBVCC") (class "Default")
      (node (ref "C11") (pin "2") (pinfunction "2_2") (pintype "passive"))
      (node (ref "F3") (pin "1") (pinfunction "1_1") (pintype "passive"))
      (node (ref "J2") (pin "VBUS") (pinfunction "VBUS_VBUS") (pintype "passive"))
      (node (ref "R4") (pin "2") (pinfunction "2_2") (pintype "passive"))
      (node (ref "U2") (pin "31") (pinfunction "UVCC_31") (pintype "passive"))
      (node (ref "U5") (pin "5") (pinfunction "VBUS_5") (pintype "passive"))
      (node (ref "USB_AUX") (pin "5") (pinfunction "5_5") (pintype "passive"))
    )
    (net (code "186") (name "VIN1") (class "Default")
      (node (ref "C1") (pin "1") (pinfunction "1_1") (pintype "passive"))
      (node (ref "C17") (pin "2") (pinfunction "2_2") (pintype "passive"))
      (node (ref "C21") (pin "1") (pinfunction "1_1") (pintype "passive"))
      (node (ref "C22") (pin "1") (pinfunction "1_1") (pintype "passive"))
      (node (ref "C23") (pin "1") (pinfunction "1_1") (pintype "passive"))
      (node (ref "C24") (pin "1") (pinfunction "1_1") (pintype "passive"))
      (node (ref "C25") (pin "1") (pinfunction "1_1") (pintype "passive"))
      (node (ref "C3") (pin "2") (pinfunction "2_2") (pintype "passive"))
      (node (ref "C30") (pin "1") (pinfunction "1_1") (pintype "passive"))
      (node (ref "D12") (pin "K") (pinfunction "K_K") (pintype "passive"))
      (node (ref "D6") (pin "K") (pinfunction "K_K") (pintype "passive"))
      (node (ref "D9") (pin "K") (pinfunction "K_K") (pintype "passive"))
      (node (ref "E0") (pin "16") (pinfunction "VMOT_16") (pintype "passive"))
      (node (ref "E1") (pin "16") (pinfunction "VMOT_16") (pintype "passive"))
      (node (ref "E2") (pin "16") (pinfunction "VMOT_16") (pintype "passive"))
      (node (ref "F2") (pin "1") (pinfunction "1_1") (pintype "passive"))
      (node (ref "HE0") (pin "1") (pinfunction "4_1") (pintype "power_in"))
      (node (ref "HE1") (pin "1") (pinfunction "4_1") (pintype "power_in"))
      (node (ref "PWR") (pin "1") (pinfunction "1_1") (pintype "passive"))
      (node (ref "U3") (pin "4") (pinfunction "~{SHDN}_4") (pintype "passive"))
      (node (ref "U3") (pin "5") (pinfunction "Vin_5") (pintype "passive"))
      (node (ref "U4") (pin "9") (pinfunction "VIN_9") (pintype "passive"))
      (node (ref "VFA0_sel") (pin "1") (pinfunction "1_1") (pintype "passive"))
      (node (ref "VFA1_sel") (pin "1") (pinfunction "1_1") (pintype "passive"))
      (node (ref "VHE2_sel") (pin "1") (pinfunction "1_1") (pintype "passive"))
      (node (ref "X") (pin "16") (pinfunction "VMOT_16") (pintype "passive"))
      (node (ref "Y") (pin "16") (pinfunction "VMOT_16") (pintype "passive"))
      (node (ref "Z") (pin "16") (pinfunction "VMOT_16") (pintype "passive"))
    )
    (net (code "187") (name "VIN2") (class "Default")
      (node (ref "D13") (pin "K") (pinfunction "K_K") (pintype "passive"))
      (node (ref "D7") (pin "K") (pinfunction "K_K") (pintype "passive"))
      (node (ref "F1") (pin "1") (pinfunction "1_1") (pintype "passive"))
      (node (ref "HB-OUT") (pin "2") (pinfunction "2_2") (pintype "power_in"))
    )
    (net (code "188") (name "unconnected-(E0_0-Pad1)") (class "Default")
      (node (ref "E0_0") (pin "1") (pinfunction "1_1") (pintype "passive"))
    )
    (net (code "189") (name "unconnected-(E0_0-Pad2)") (class "Default")
      (node (ref "E0_0") (pin "2") (pinfunction "2_2") (pintype "passive"))
    )
    (net (code "190") (name "unconnected-(E0_0-Pad3)") (class "Default")
      (node (ref "E0_0") (pin "3") (pinfunction "3_3") (pintype "passive"))
    )
    (net (code "191") (name "unconnected-(E0_0-Pad4)") (class "Default")
      (node (ref "E0_0") (pin "4") (pinfunction "4_4") (pintype "passive"))
    )
    (net (code "192") (name "unconnected-(E0_0-Pad5)") (class "Default")
      (node (ref "E0_0") (pin "5") (pinfunction "5_5") (pintype "passive"))
    )
    (net (code "193") (name "unconnected-(E0_0-Pad6)") (class "Default")
      (node (ref "E0_0") (pin "6") (pinfunction "6_6") (pintype "passive"))
    )
    (net (code "194") (name "unconnected-(E0_0-Pad7)") (class "Default")
      (node (ref "E0_0") (pin "7") (pinfunction "7_7") (pintype "passive"))
    )
    (net (code "195") (name "unconnected-(E0_0-Pad8)") (class "Default")
      (node (ref "E0_0") (pin "8") (pinfunction "8_8") (pintype "passive"))
    )
    (net (code "196") (name "unconnected-(E0_1-Pad1)") (class "Default")
      (node (ref "E0_1") (pin "1") (pinfunction "1_1") (pintype "passive"))
    )
    (net (code "197") (name "unconnected-(E0_1-Pad2)") (class "Default")
      (node (ref "E0_1") (pin "2") (pinfunction "2_2") (pintype "passive"))
    )
    (net (code "198") (name "unconnected-(E0_1-Pad3)") (class "Default")
      (node (ref "E0_1") (pin "3") (pinfunction "3_3") (pintype "passive"))
    )
    (net (code "199") (name "unconnected-(E0_1-Pad4)") (class "Default")
      (node (ref "E0_1") (pin "4") (pinfunction "4_4") (pintype "passive"))
    )
    (net (code "200") (name "unconnected-(E0_1-Pad5)") (class "Default")
      (node (ref "E0_1") (pin "5") (pinfunction "5_5") (pintype "passive"))
    )
    (net (code "201") (name "unconnected-(E0_1-Pad6)") (class "Default")
      (node (ref "E0_1") (pin "6") (pinfunction "6_6") (pintype "passive"))
    )
    (net (code "202") (name "unconnected-(E0_1-Pad7)") (class "Default")
      (node (ref "E0_1") (pin "7") (pinfunction "7_7") (pintype "passive"))
    )
    (net (code "203") (name "unconnected-(E0_1-Pad8)") (class "Default")
      (node (ref "E0_1") (pin "8") (pinfunction "8_8") (pintype "passive"))
    )
    (net (code "204") (name "unconnected-(E1_0-Pad1)") (class "Default")
      (node (ref "E1_0") (pin "1") (pinfunction "1_1") (pintype "passive"))
    )
    (net (code "205") (name "unconnected-(E1_0-Pad2)") (class "Default")
      (node (ref "E1_0") (pin "2") (pinfunction "2_2") (pintype "passive"))
    )
    (net (code "206") (name "unconnected-(E1_0-Pad3)") (class "Default")
      (node (ref "E1_0") (pin "3") (pinfunction "3_3") (pintype "passive"))
    )
    (net (code "207") (name "unconnected-(E1_0-Pad4)") (class "Default")
      (node (ref "E1_0") (pin "4") (pinfunction "4_4") (pintype "passive"))
    )
    (net (code "208") (name "unconnected-(E1_0-Pad5)") (class "Default")
      (node (ref "E1_0") (pin "5") (pinfunction "5_5") (pintype "passive"))
    )
    (net (code "209") (name "unconnected-(E1_0-Pad6)") (class "Default")
      (node (ref "E1_0") (pin "6") (pinfunction "6_6") (pintype "passive"))
    )
    (net (code "210") (name "unconnected-(E1_0-Pad7)") (class "Default")
      (node (ref "E1_0") (pin "7") (pinfunction "7_7") (pintype "passive"))
    )
    (net (code "211") (name "unconnected-(E1_0-Pad8)") (class "Default")
      (node (ref "E1_0") (pin "8") (pinfunction "8_8") (pintype "passive"))
    )
    (net (code "212") (name "unconnected-(E1_1-Pad1)") (class "Default")
      (node (ref "E1_1") (pin "1") (pinfunction "1_1") (pintype "passive"))
    )
    (net (code "213") (name "unconnected-(E1_1-Pad2)") (class "Default")
      (node (ref "E1_1") (pin "2") (pinfunction "2_2") (pintype "passive"))
    )
    (net (code "214") (name "unconnected-(E1_1-Pad3)") (class "Default")
      (node (ref "E1_1") (pin "3") (pinfunction "3_3") (pintype "passive"))
    )
    (net (code "215") (name "unconnected-(E1_1-Pad4)") (class "Default")
      (node (ref "E1_1") (pin "4") (pinfunction "4_4") (pintype "passive"))
    )
    (net (code "216") (name "unconnected-(E1_1-Pad5)") (class "Default")
      (node (ref "E1_1") (pin "5") (pinfunction "5_5") (pintype "passive"))
    )
    (net (code "217") (name "unconnected-(E1_1-Pad6)") (class "Default")
      (node (ref "E1_1") (pin "6") (pinfunction "6_6") (pintype "passive"))
    )
    (net (code "218") (name "unconnected-(E1_1-Pad7)") (class "Default")
      (node (ref "E1_1") (pin "7") (pinfunction "7_7") (pintype "passive"))
    )
    (net (code "219") (name "unconnected-(E1_1-Pad8)") (class "Default")
      (node (ref "E1_1") (pin "8") (pinfunction "8_8") (pintype "passive"))
    )
    (net (code "220") (name "unconnected-(E2_0-Pad1)") (class "Default")
      (node (ref "E2_0") (pin "1") (pinfunction "1_1") (pintype "passive"))
    )
    (net (code "221") (name "unconnected-(E2_0-Pad2)") (class "Default")
      (node (ref "E2_0") (pin "2") (pinfunction "2_2") (pintype "passive"))
    )
    (net (code "222") (name "unconnected-(E2_0-Pad3)") (class "Default")
      (node (ref "E2_0") (pin "3") (pinfunction "3_3") (pintype "passive"))
    )
    (net (code "223") (name "unconnected-(E2_0-Pad4)") (class "Default")
      (node (ref "E2_0") (pin "4") (pinfunction "4_4") (pintype "passive"))
    )
    (net (code "224") (name "unconnected-(E2_0-Pad5)") (class "Default")
      (node (ref "E2_0") (pin "5") (pinfunction "5_5") (pintype "passive"))
    )
    (net (code "225") (name "unconnected-(E2_0-Pad6)") (class "Default")
      (node (ref "E2_0") (pin "6") (pinfunction "6_6") (pintype "passive"))
    )
    (net (code "226") (name "unconnected-(E2_0-Pad7)") (class "Default")
      (node (ref "E2_0") (pin "7") (pinfunction "7_7") (pintype "passive"))
    )
    (net (code "227") (name "unconnected-(E2_0-Pad8)") (class "Default")
      (node (ref "E2_0") (pin "8") (pinfunction "8_8") (pintype "passive"))
    )
    (net (code "228") (name "unconnected-(E2_1-Pad1)") (class "Default")
      (node (ref "E2_1") (pin "1") (pinfunction "1_1") (pintype "passive"))
    )
    (net (code "229") (name "unconnected-(E2_1-Pad2)") (class "Default")
      (node (ref "E2_1") (pin "2") (pinfunction "2_2") (pintype "passive"))
    )
    (net (code "230") (name "unconnected-(E2_1-Pad3)") (class "Default")
      (node (ref "E2_1") (pin "3") (pinfunction "3_3") (pintype "passive"))
    )
    (net (code "231") (name "unconnected-(E2_1-Pad4)") (class "Default")
      (node (ref "E2_1") (pin "4") (pinfunction "4_4") (pintype "passive"))
    )
    (net (code "232") (name "unconnected-(E2_1-Pad5)") (class "Default")
      (node (ref "E2_1") (pin "5") (pinfunction "5_5") (pintype "passive"))
    )
    (net (code "233") (name "unconnected-(E2_1-Pad6)") (class "Default")
      (node (ref "E2_1") (pin "6") (pinfunction "6_6") (pintype "passive"))
    )
    (net (code "234") (name "unconnected-(E2_1-Pad7)") (class "Default")
      (node (ref "E2_1") (pin "7") (pinfunction "7_7") (pintype "passive"))
    )
    (net (code "235") (name "unconnected-(E2_1-Pad8)") (class "Default")
      (node (ref "E2_1") (pin "8") (pinfunction "8_8") (pintype "passive"))
    )
    (net (code "236") (name "unconnected-(J2-PadID)") (class "Default")
      (node (ref "J2") (pin "ID") (pinfunction "ID_ID") (pintype "passive"))
    )
    (net (code "237") (name "unconnected-(JTAG-Pad8)") (class "Default")
      (node (ref "JTAG") (pin "8") (pinfunction "8_8") (pintype "passive+no_connect"))
    )
    (net (code "238") (name "unconnected-(U1-(CLKO{slash}ICP3{slash}INT7)PE7-Pad9)") (class "Default")
      (node (ref "U1") (pin "9") (pinfunction "(CLKO/ICP3/INT7)PE7_9") (pintype "passive+no_connect"))
    )
    (net (code "239") (name "unconnected-(U1-(ICP1)PD4-Pad47)") (class "Default")
      (node (ref "U1") (pin "47") (pinfunction "(ICP1)PD4_47") (pintype "passive+no_connect"))
    )
    (net (code "240") (name "unconnected-(U1-(OC2A{slash}PCINT4)PB4-Pad23)") (class "Default")
      (node (ref "U1") (pin "23") (pinfunction "(OC2A/PCINT4)PB4_23") (pintype "passive"))
    )
    (net (code "241") (name "unconnected-(U1-(T1)PD6-Pad49)") (class "Default")
      (node (ref "U1") (pin "49") (pinfunction "(T1)PD6_49") (pintype "passive+no_connect"))
    )
    (net (code "242") (name "unconnected-(U1-(T3{slash}INT6)PE6-Pad8)") (class "Default")
      (node (ref "U1") (pin "8") (pinfunction "(T3/INT6)PE6_8") (pintype "passive+no_connect"))
    )
    (net (code "243") (name "unconnected-(U1-(TOSC1)PG4-Pad29)") (class "Default")
      (node (ref "U1") (pin "29") (pinfunction "(TOSC1)PG4_29") (pintype "passive+no_connect"))
    )
    (net (code "244") (name "unconnected-(U1-(TOSC2)PG3-Pad28)") (class "Default")
      (node (ref "U1") (pin "28") (pinfunction "(TOSC2)PG3_28") (pintype "passive+no_connect"))
    )
    (net (code "245") (name "unconnected-(U1-(XCK1)PD5-Pad48)") (class "Default")
      (node (ref "U1") (pin "48") (pinfunction "(XCK1)PD5_48") (pintype "passive+no_connect"))
    )
    (net (code "246") (name "unconnected-(U1-PH2(XCK2)-Pad14)") (class "Default")
      (node (ref "U1") (pin "14") (pinfunction "PH2(XCK2)_14") (pintype "passive+no_connect"))
    )
    (net (code "247") (name "unconnected-(U1-PH7(T4)-Pad27)") (class "Default")
      (node (ref "U1") (pin "27") (pinfunction "PH7(T4)_27") (pintype "passive+no_connect"))
    )
    (net (code "248") (name "unconnected-(U1-PJ2(XCK3{slash}PCINT11)-Pad65)") (class "Default")
      (node (ref "U1") (pin "65") (pinfunction "PJ2(XCK3/PCINT11)_65") (pintype "passive+no_connect"))
    )
    (net (code "249") (name "unconnected-(U1-PJ3(PCINT12)-Pad66)") (class "Default")
      (node (ref "U1") (pin "66") (pinfunction "PJ3(PCINT12)_66") (pintype "passive+no_connect"))
    )
    (net (code "250") (name "unconnected-(U1-PJ4(PCINT13)-Pad67)") (class "Default")
      (node (ref "U1") (pin "67") (pinfunction "PJ4(PCINT13)_67") (pintype "passive+no_connect"))
    )
    (net (code "251") (name "unconnected-(U1-PJ5(PCINT14)-Pad68)") (class "Default")
      (node (ref "U1") (pin "68") (pinfunction "PJ5(PCINT14)_68") (pintype "passive+no_connect"))
    )
    (net (code "252") (name "unconnected-(U1-PJ6(PCINT15)-Pad69)") (class "Default")
      (node (ref "U1") (pin "69") (pinfunction "PJ6(PCINT15)_69") (pintype "passive+no_connect"))
    )
    (net (code "253") (name "unconnected-(U1-PJ7-Pad79)") (class "Default")
      (node (ref "U1") (pin "79") (pinfunction "PJ7_79") (pintype "passive+no_connect"))
    )
    (net (code "254") (name "unconnected-(U2-(AIN0{slash}INT1)PD1-Pad7)") (class "Default")
      (node (ref "U2") (pin "7") (pinfunction "(AIN0/INT1)PD1_7") (pintype "passive+no_connect"))
    )
    (net (code "255") (name "unconnected-(U2-(AIN2{slash}PCINT11)PC2-Pad5)") (class "Default")
      (node (ref "U2") (pin "5") (pinfunction "(AIN2/PCINT11)PC2_5") (pintype "passive+no_connect"))
    )
    (net (code "256") (name "unconnected-(U2-(INT4{slash}ICP1{slash}CLK0)PC7-Pad22)") (class "Default")
      (node (ref "U2") (pin "22") (pinfunction "(INT4/ICP1/CLK0)PC7_22") (pintype "passive+no_connect"))
    )
    (net (code "257") (name "unconnected-(U2-(OC0B{slash}INT0)PD0-Pad6)") (class "Default")
      (node (ref "U2") (pin "6") (pinfunction "(OC0B/INT0)PD0_6") (pintype "passive+no_connect"))
    )
    (net (code "258") (name "unconnected-(U2-(OC1A{slash}PCINT8)PC6-Pad23)") (class "Default")
      (node (ref "U2") (pin "23") (pinfunction "(OC1A/PCINT8)PC6_23") (pintype "passive+no_connect"))
    )
    (net (code "259") (name "unconnected-(U2-(PCINT5)PB5-Pad19)") (class "Default")
      (node (ref "U2") (pin "19") (pinfunction "(PCINT5)PB5_19") (pintype "passive+no_connect"))
    )
    (net (code "260") (name "unconnected-(U2-(PCINT6)PB6-Pad20)") (class "Default")
      (node (ref "U2") (pin "20") (pinfunction "(PCINT6)PB6_20") (pintype "passive+no_connect"))
    )
    (net (code "261") (name "unconnected-(U2-(PCINT7{slash}OC0A{slash}OC1C)PB7-Pad21)") (class "Default")
      (node (ref "U2") (pin "21") (pinfunction "(PCINT7/OC0A/OC1C)PB7_21") (pintype "passive+no_connect"))
    )
    (net (code "262") (name "unconnected-(U2-(PCINT9{slash}OC1B)PC5-Pad25)") (class "Default")
      (node (ref "U2") (pin "25") (pinfunction "(PCINT9/OC1B)PC5_25") (pintype "passive+no_connect"))
    )
    (net (code "263") (name "unconnected-(U2-(PCINT10)PC4-Pad26)") (class "Default")
      (node (ref "U2") (pin "26") (pinfunction "(PCINT10)PC4_26") (pintype "passive+no_connect"))
    )
    (net (code "264") (name "unconnected-(U2-(RTS{slash}AIN5{slash}INT6)PD6-Pad12)") (class "Default")
      (node (ref "U2") (pin "12") (pinfunction "(RTS/AIN5/INT6)PD6_12") (pintype "passive+no_connect"))
    )
    (net (code "265") (name "unconnected-(U2-(SS{slash}PCINT0)PB0-Pad14)") (class "Default")
      (node (ref "U2") (pin "14") (pinfunction "(SS/PCINT0)PB0_14") (pintype "passive+no_connect"))
    )
    (net (code "266") (name "unconnected-(U2-(T1{slash}PCINT4)PB4-Pad18)") (class "Default")
      (node (ref "U2") (pin "18") (pinfunction "(T1/PCINT4)PB4_18") (pintype "passive+no_connect"))
    )
    (net (code "267") (name "unconnected-(U5-IO3-Pad4)") (class "Default")
      (node (ref "U5") (pin "4") (pinfunction "IO3_4") (pintype "passive+no_connect"))
    )
    (net (code "268") (name "unconnected-(U5-IO4-Pad6)") (class "Default")
      (node (ref "U5") (pin "6") (pinfunction "IO4_6") (pintype "passive+no_connect"))
    )
    (net (code "269") (name "unconnected-(X_1-Pad1)") (class "Default")
      (node (ref "X_1") (pin "1") (pinfunction "1_1") (pintype "passive"))
    )
    (net (code "270") (name "unconnected-(X_1-Pad2)") (class "Default")
      (node (ref "X_1") (pin "2") (pinfunction "2_2") (pintype "passive"))
    )
    (net (code "271") (name "unconnected-(X_1-Pad3)") (class "Default")
      (node (ref "X_1") (pin "3") (pinfunction "3_3") (pintype "passive"))
    )
    (net (code "272") (name "unconnected-(X_1-Pad4)") (class "Default")
      (node (ref "X_1") (pin "4") (pinfunction "4_4") (pintype "passive"))
    )
    (net (code "273") (name "unconnected-(X_1-Pad5)") (class "Default")
      (node (ref "X_1") (pin "5") (pinfunction "5_5") (pintype "passive"))
    )
    (net (code "274") (name "unconnected-(X_1-Pad6)") (class "Default")
      (node (ref "X_1") (pin "6") (pinfunction "6_6") (pintype "passive"))
    )
    (net (code "275") (name "unconnected-(X_1-Pad7)") (class "Default")
      (node (ref "X_1") (pin "7") (pinfunction "7_7") (pintype "passive"))
    )
    (net (code "276") (name "unconnected-(X_1-Pad8)") (class "Default")
      (node (ref "X_1") (pin "8") (pinfunction "8_8") (pintype "passive"))
    )
    (net (code "277") (name "unconnected-(X_2-Pad1)") (class "Default")
      (node (ref "X_2") (pin "1") (pinfunction "1_1") (pintype "passive"))
    )
    (net (code "278") (name "unconnected-(X_2-Pad2)") (class "Default")
      (node (ref "X_2") (pin "2") (pinfunction "2_2") (pintype "passive"))
    )
    (net (code "279") (name "unconnected-(X_2-Pad3)") (class "Default")
      (node (ref "X_2") (pin "3") (pinfunction "3_3") (pintype "passive"))
    )
    (net (code "280") (name "unconnected-(X_2-Pad4)") (class "Default")
      (node (ref "X_2") (pin "4") (pinfunction "4_4") (pintype "passive"))
    )
    (net (code "281") (name "unconnected-(X_2-Pad5)") (class "Default")
      (node (ref "X_2") (pin "5") (pinfunction "5_5") (pintype "passive"))
    )
    (net (code "282") (name "unconnected-(X_2-Pad6)") (class "Default")
      (node (ref "X_2") (pin "6") (pinfunction "6_6") (pintype "passive"))
    )
    (net (code "283") (name "unconnected-(X_2-Pad7)") (class "Default")
      (node (ref "X_2") (pin "7") (pinfunction "7_7") (pintype "passive"))
    )
    (net (code "284") (name "unconnected-(X_2-Pad8)") (class "Default")
      (node (ref "X_2") (pin "8") (pinfunction "8_8") (pintype "passive"))
    )
    (net (code "285") (name "unconnected-(Y_0-Pad1)") (class "Default")
      (node (ref "Y_0") (pin "1") (pinfunction "1_1") (pintype "passive"))
    )
    (net (code "286") (name "unconnected-(Y_0-Pad2)") (class "Default")
      (node (ref "Y_0") (pin "2") (pinfunction "2_2") (pintype "passive"))
    )
    (net (code "287") (name "unconnected-(Y_0-Pad3)") (class "Default")
      (node (ref "Y_0") (pin "3") (pinfunction "3_3") (pintype "passive"))
    )
    (net (code "288") (name "unconnected-(Y_0-Pad4)") (class "Default")
      (node (ref "Y_0") (pin "4") (pinfunction "4_4") (pintype "passive"))
    )
    (net (code "289") (name "unconnected-(Y_0-Pad5)") (class "Default")
      (node (ref "Y_0") (pin "5") (pinfunction "5_5") (pintype "passive"))
    )
    (net (code "290") (name "unconnected-(Y_0-Pad6)") (class "Default")
      (node (ref "Y_0") (pin "6") (pinfunction "6_6") (pintype "passive"))
    )
    (net (code "291") (name "unconnected-(Y_0-Pad7)") (class "Default")
      (node (ref "Y_0") (pin "7") (pinfunction "7_7") (pintype "passive"))
    )
    (net (code "292") (name "unconnected-(Y_0-Pad8)") (class "Default")
      (node (ref "Y_0") (pin "8") (pinfunction "8_8") (pintype "passive"))
    )
    (net (code "293") (name "unconnected-(Y_1-Pad1)") (class "Default")
      (node (ref "Y_1") (pin "1") (pinfunction "1_1") (pintype "passive"))
    )
    (net (code "294") (name "unconnected-(Y_1-Pad2)") (class "Default")
      (node (ref "Y_1") (pin "2") (pinfunction "2_2") (pintype "passive"))
    )
    (net (code "295") (name "unconnected-(Y_1-Pad3)") (class "Default")
      (node (ref "Y_1") (pin "3") (pinfunction "3_3") (pintype "passive"))
    )
    (net (code "296") (name "unconnected-(Y_1-Pad4)") (class "Default")
      (node (ref "Y_1") (pin "4") (pinfunction "4_4") (pintype "passive"))
    )
    (net (code "297") (name "unconnected-(Y_1-Pad5)") (class "Default")
      (node (ref "Y_1") (pin "5") (pinfunction "5_5") (pintype "passive"))
    )
    (net (code "298") (name "unconnected-(Y_1-Pad6)") (class "Default")
      (node (ref "Y_1") (pin "6") (pinfunction "6_6") (pintype "passive"))
    )
    (net (code "299") (name "unconnected-(Y_1-Pad7)") (class "Default")
      (node (ref "Y_1") (pin "7") (pinfunction "7_7") (pintype "passive"))
    )
    (net (code "300") (name "unconnected-(Y_1-Pad8)") (class "Default")
      (node (ref "Y_1") (pin "8") (pinfunction "8_8") (pintype "passive"))
    )
    (net (code "301") (name "unconnected-(Z_0-Pad1)") (class "Default")
      (node (ref "Z_0") (pin "1") (pinfunction "1_1") (pintype "passive"))
    )
    (net (code "302") (name "unconnected-(Z_0-Pad2)") (class "Default")
      (node (ref "Z_0") (pin "2") (pinfunction "2_2") (pintype "passive"))
    )
    (net (code "303") (name "unconnected-(Z_0-Pad3)") (class "Default")
      (node (ref "Z_0") (pin "3") (pinfunction "3_3") (pintype "passive"))
    )
    (net (code "304") (name "unconnected-(Z_0-Pad4)") (class "Default")
      (node (ref "Z_0") (pin "4") (pinfunction "4_4") (pintype "passive"))
    )
    (net (code "305") (name "unconnected-(Z_0-Pad5)") (class "Default")
      (node (ref "Z_0") (pin "5") (pinfunction "5_5") (pintype "passive"))
    )
    (net (code "306") (name "unconnected-(Z_0-Pad6)") (class "Default")
      (node (ref "Z_0") (pin "6") (pinfunction "6_6") (pintype "passive"))
    )
    (net (code "307") (name "unconnected-(Z_0-Pad7)") (class "Default")
      (node (ref "Z_0") (pin "7") (pinfunction "7_7") (pintype "passive"))
    )
    (net (code "308") (name "unconnected-(Z_0-Pad8)") (class "Default")
      (node (ref "Z_0") (pin "8") (pinfunction "8_8") (pintype "passive"))
    )
    (net (code "309") (name "unconnected-(Z_1-Pad1)") (class "Default")
      (node (ref "Z_1") (pin "1") (pinfunction "1_1") (pintype "passive"))
    )
    (net (code "310") (name "unconnected-(Z_1-Pad2)") (class "Default")
      (node (ref "Z_1") (pin "2") (pinfunction "2_2") (pintype "passive"))
    )
    (net (code "311") (name "unconnected-(Z_1-Pad3)") (class "Default")
      (node (ref "Z_1") (pin "3") (pinfunction "3_3") (pintype "passive"))
    )
    (net (code "312") (name "unconnected-(Z_1-Pad4)") (class "Default")
      (node (ref "Z_1") (pin "4") (pinfunction "4_4") (pintype "passive"))
    )
    (net (code "313") (name "unconnected-(Z_1-Pad5)") (class "Default")
      (node (ref "Z_1") (pin "5") (pinfunction "5_5") (pintype "passive"))
    )
    (net (code "314") (name "unconnected-(Z_1-Pad6)") (class "Default")
      (node (ref "Z_1") (pin "6") (pinfunction "6_6") (pintype "passive"))
    )
    (net (code "315") (name "unconnected-(Z_1-Pad7)") (class "Default")
      (node (ref "Z_1") (pin "7") (pinfunction "7_7") (pintype "passive"))
    )
    (net (code "316") (name "unconnected-(Z_1-Pad8)") (class "Default")
      (node (ref "Z_1") (pin "8") (pinfunction "8_8") (pintype "passive"))
    )
  )
)
